# motoretc.net
KiCad netlist of a schematic drawn in EAGLE
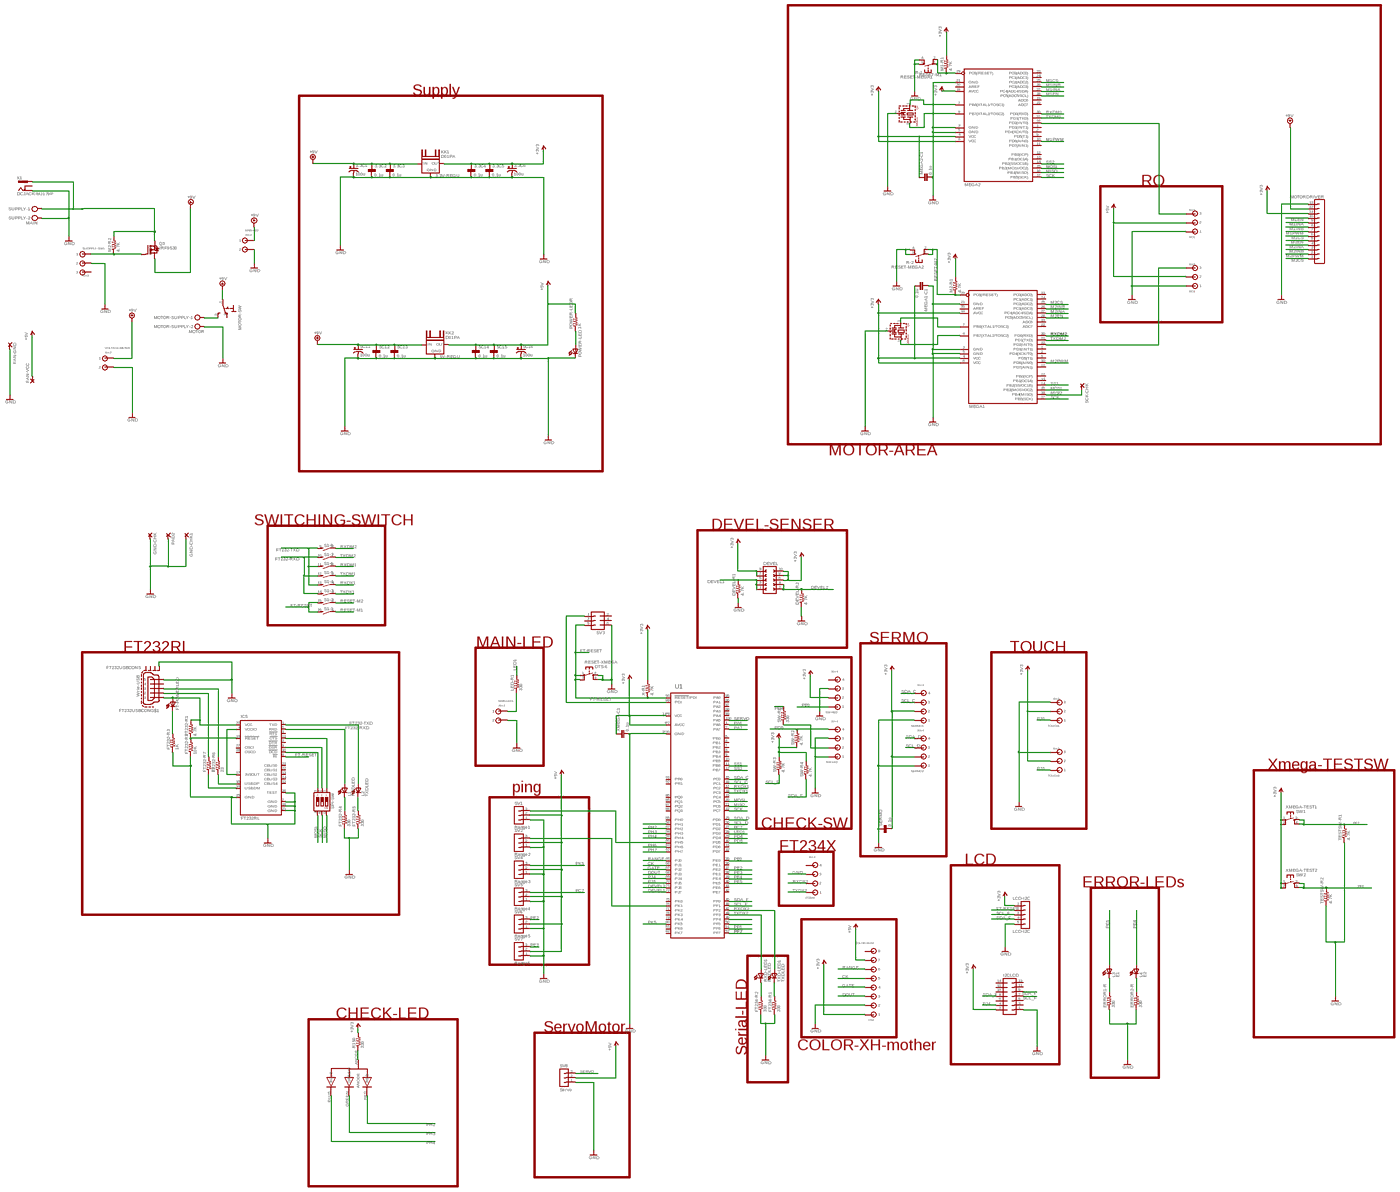
[diagram p0: schematic, sheet 1, overview]
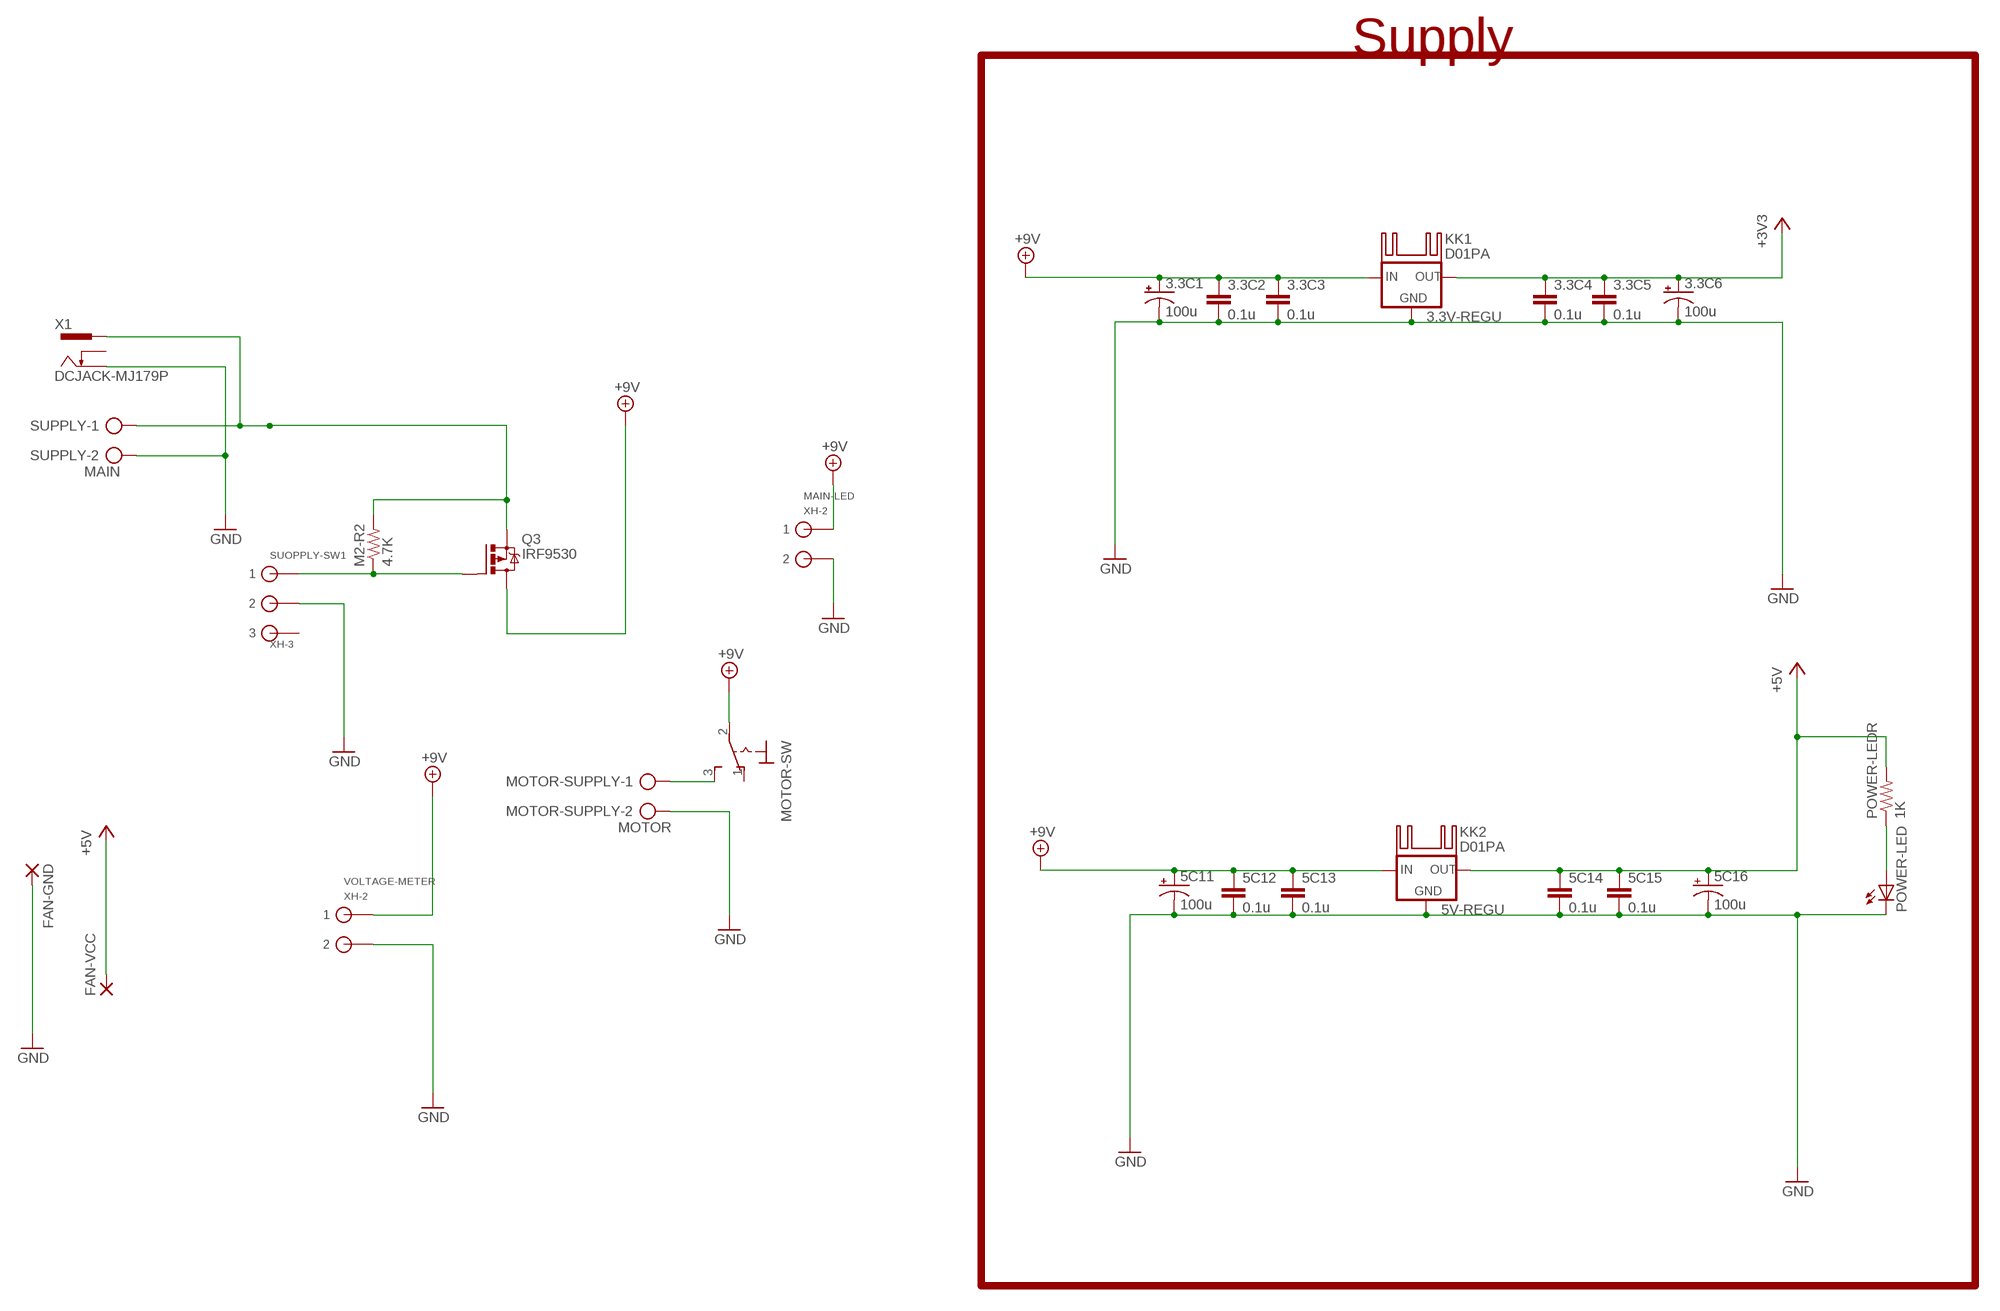
[diagram p1: schematic, sheet 1, part 1 of 4]
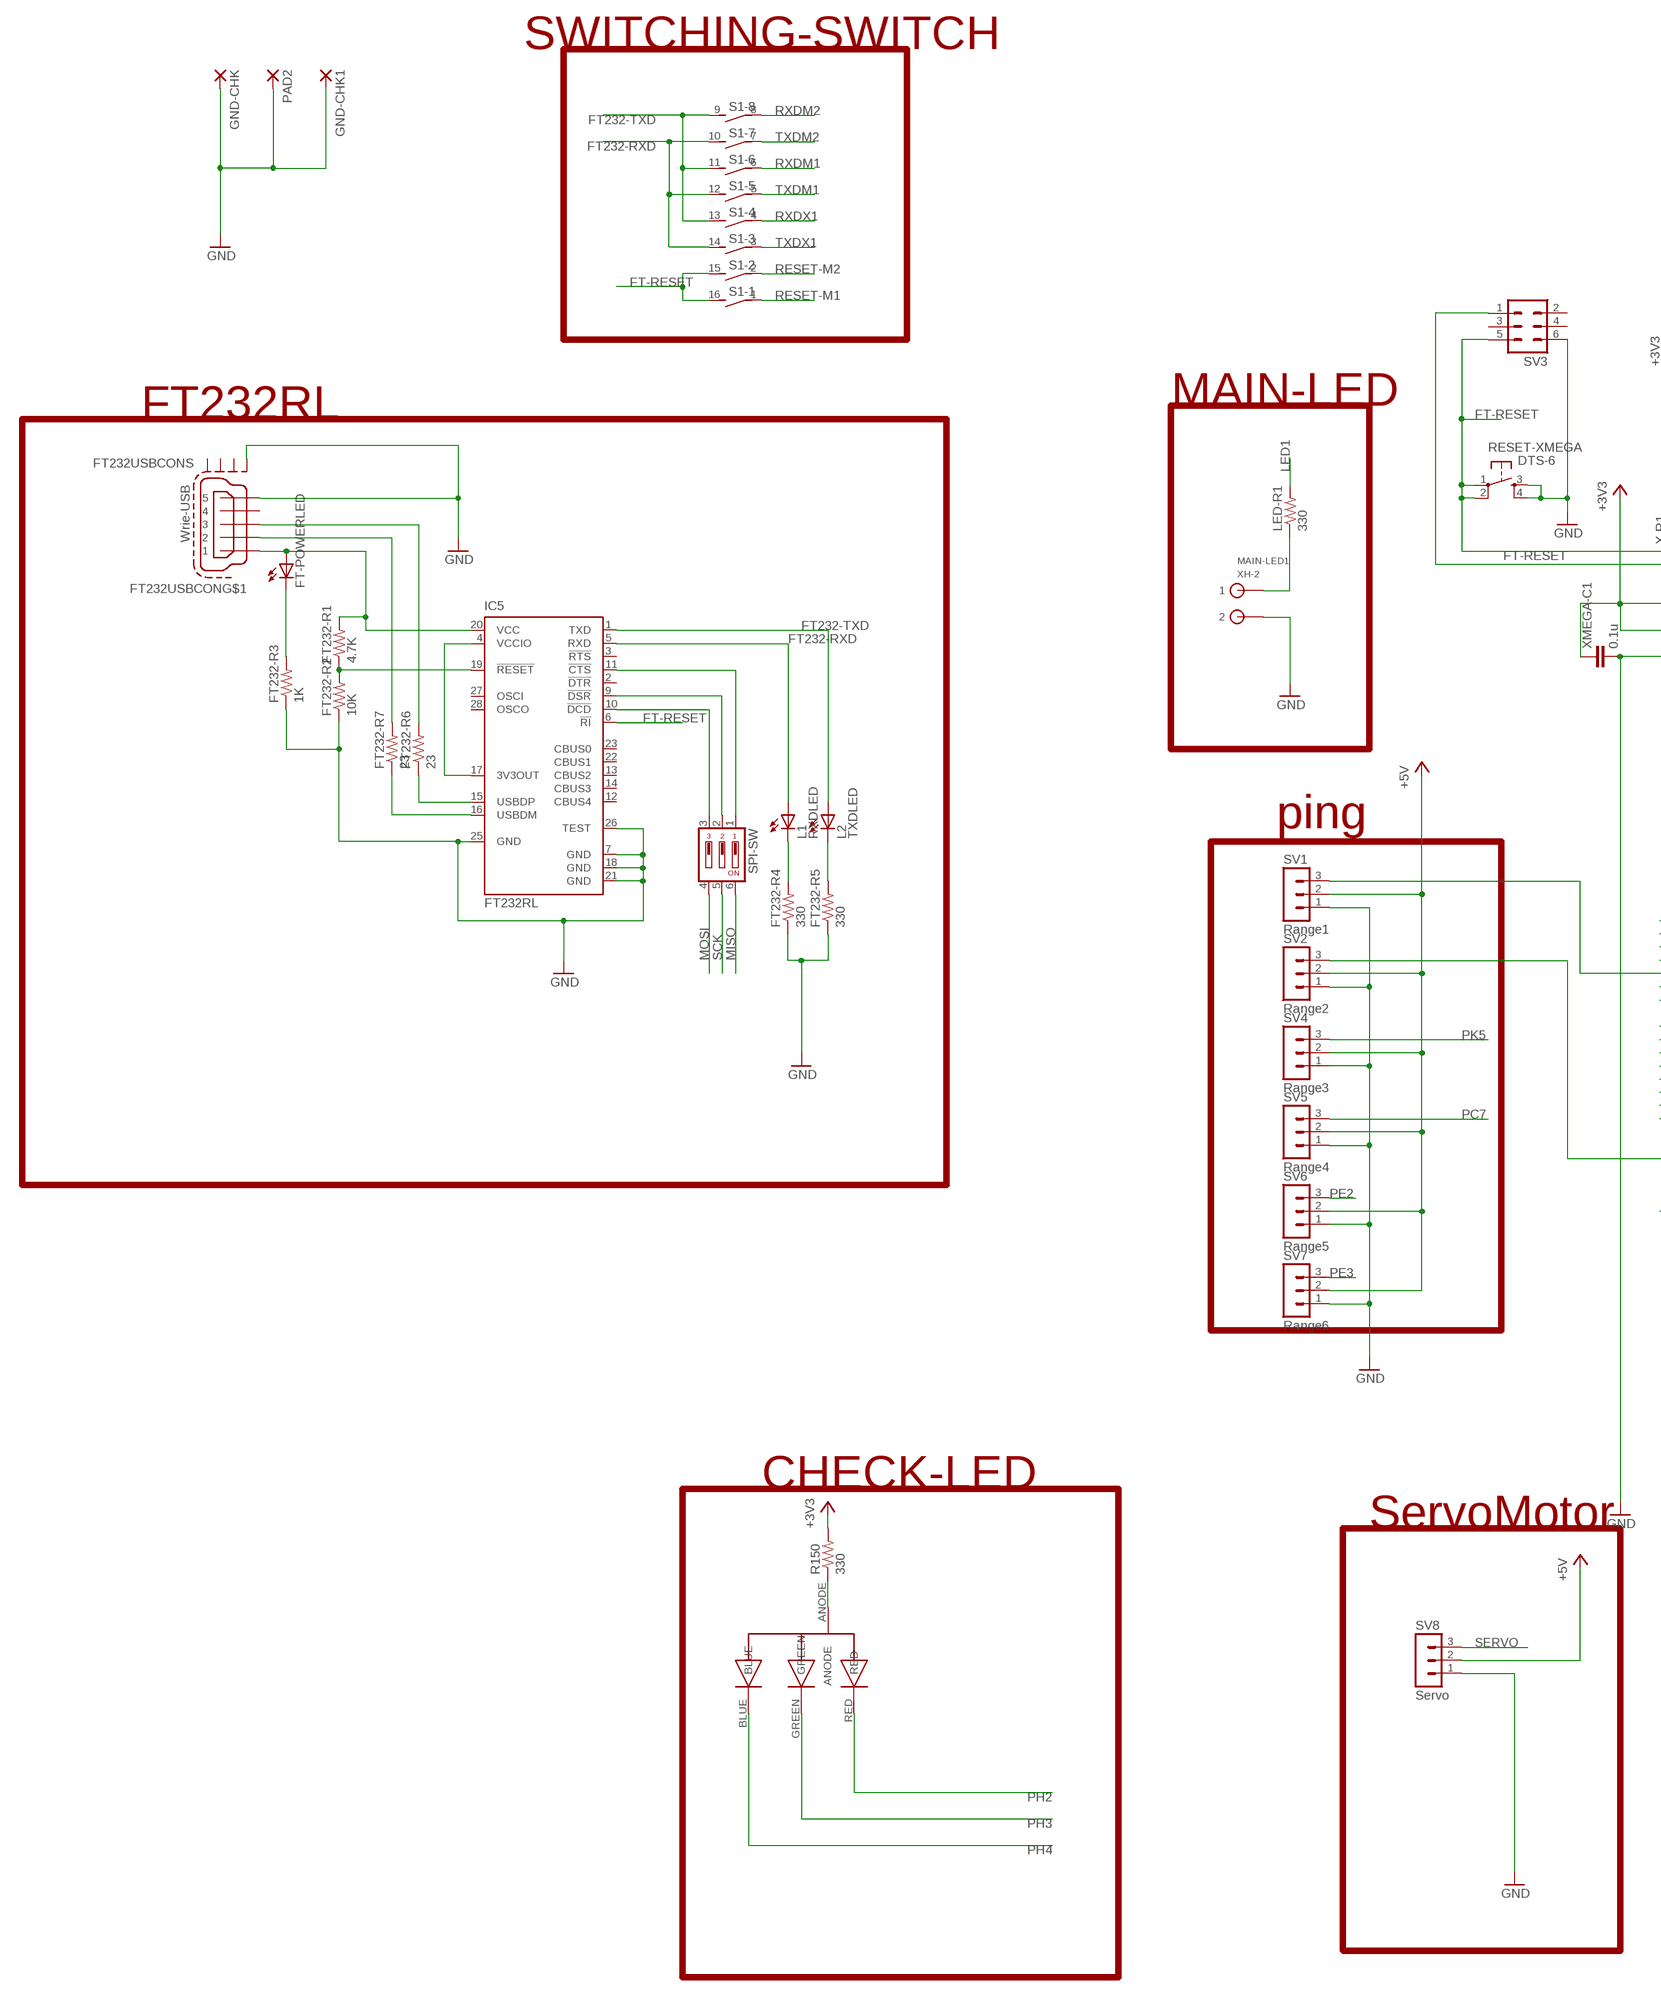
[diagram p2: schematic, sheet 1, part 2 of 4]
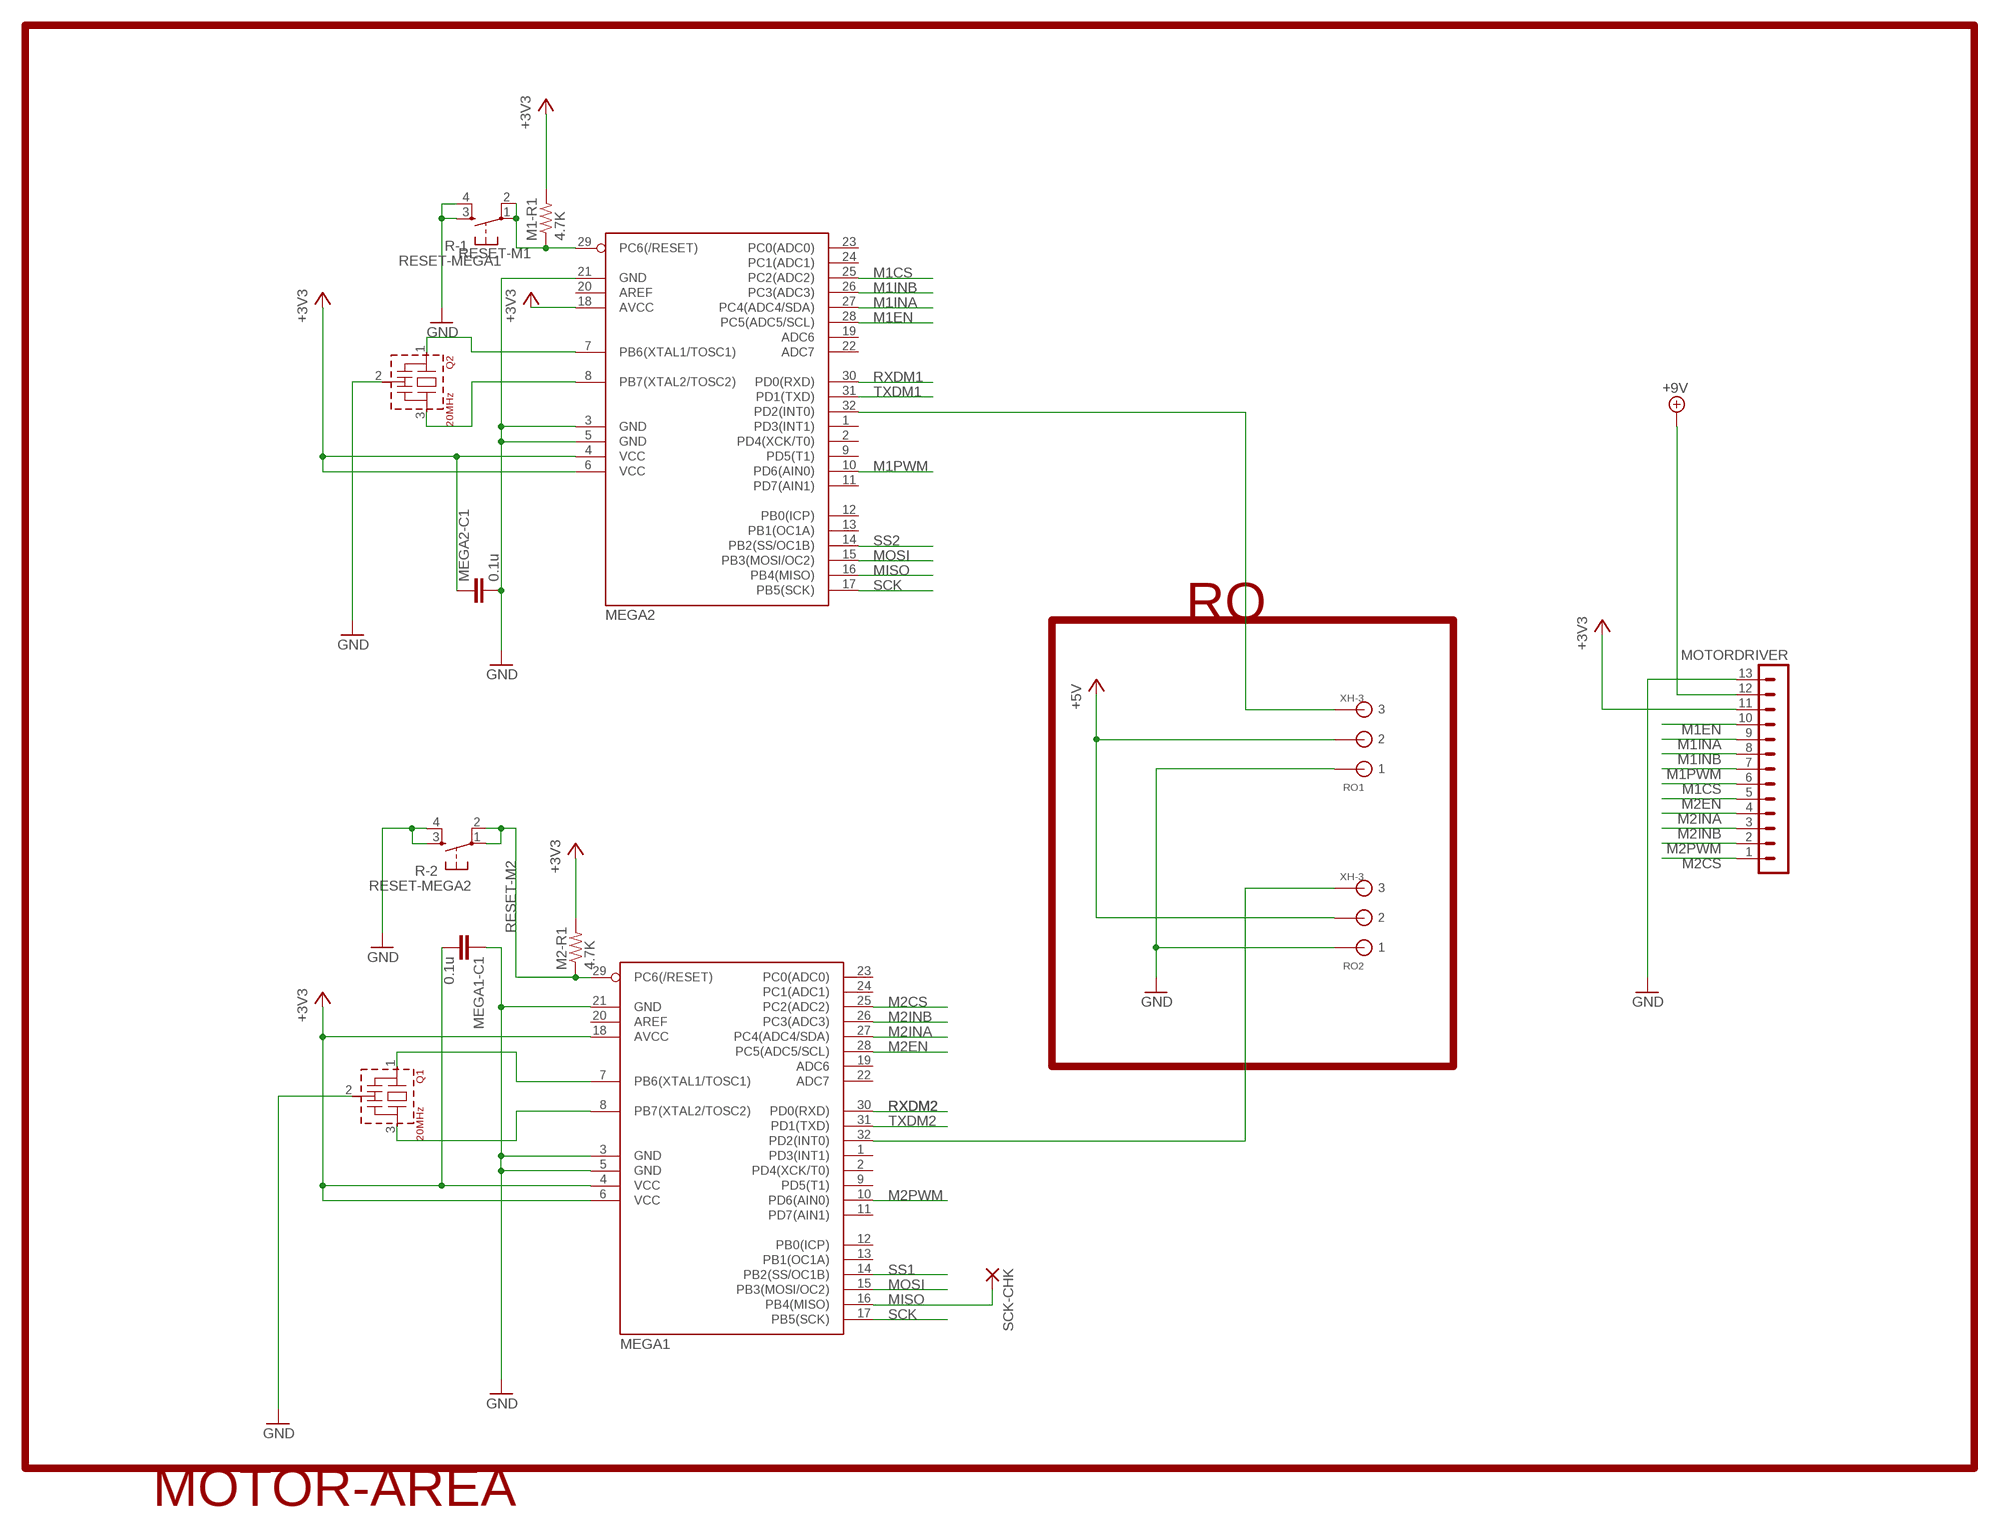
[diagram p3: schematic, sheet 1, part 3 of 4]
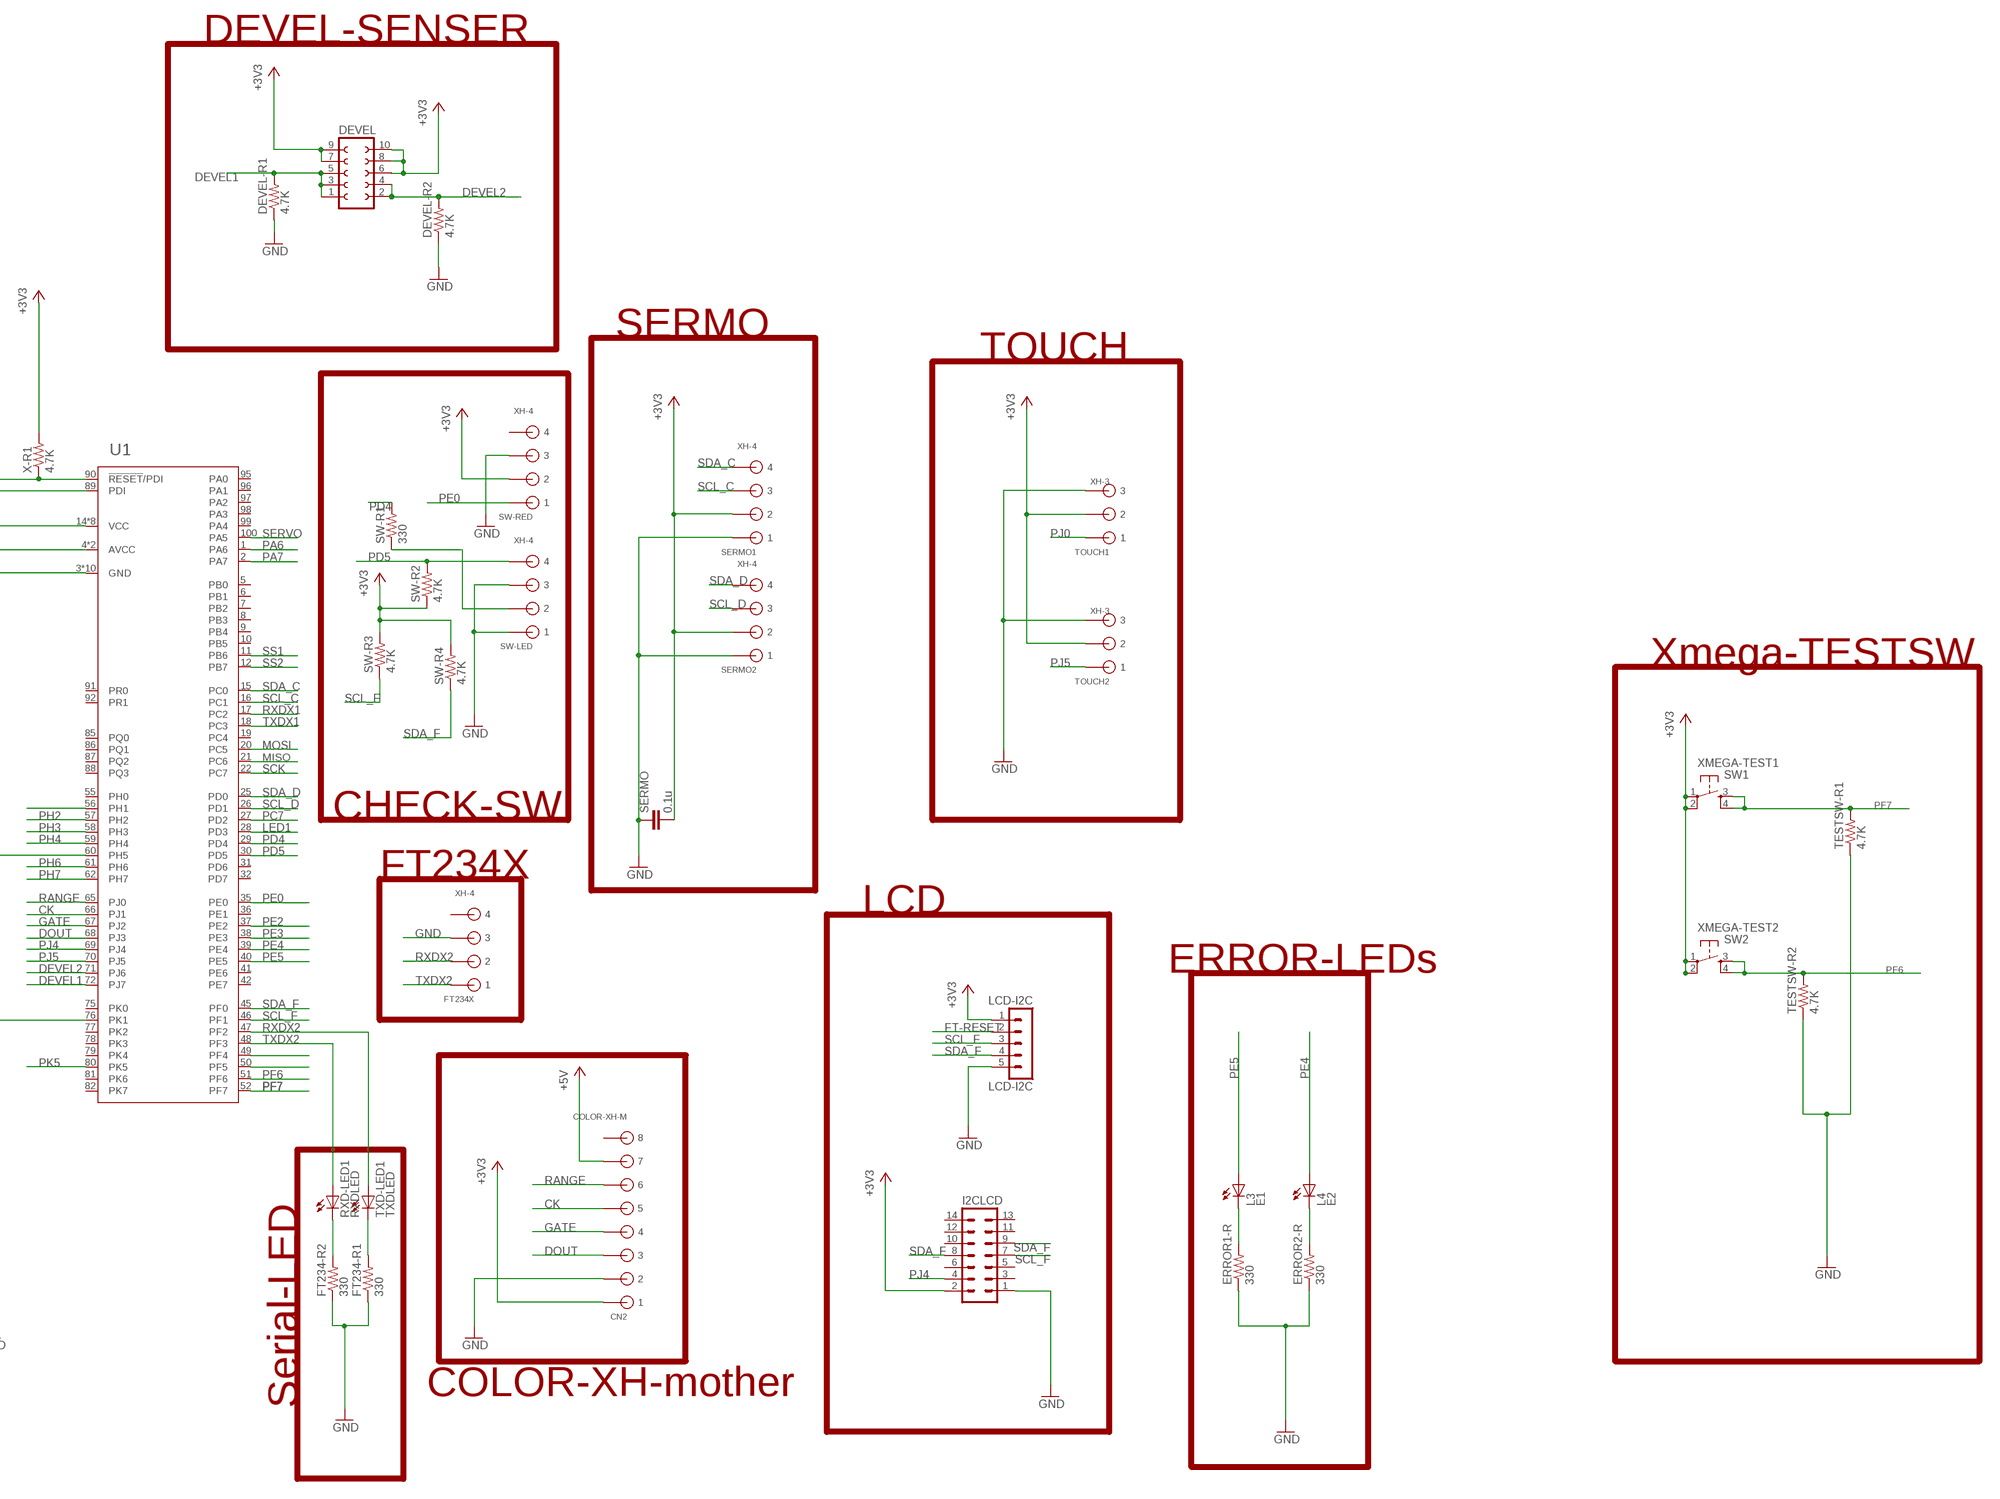
[diagram p4: schematic, sheet 1, part 4 of 4]

(export (version "E")
  (design (tool "Eeschema 10.0.6"))
  (components
    (comp (ref "3.3C1")
      (value "100u")
      (footprint "eagle-import:E2,5-6")
      (libsource (lib "eagle-import") (part "CPOL-USE2.5-6"))
    )
    (comp (ref "3.3C2")
      (value "0.1u")
      (footprint "eagle-import:C0805")
      (libsource (lib "eagle-import") (part "C-EUC0805"))
    )
    (comp (ref "3.3C3")
      (value "0.1u")
      (footprint "eagle-import:C0805")
      (libsource (lib "eagle-import") (part "C-EUC0805"))
    )
    (comp (ref "3.3C4")
      (value "0.1u")
      (footprint "eagle-import:C0805")
      (libsource (lib "eagle-import") (part "C-EUC0805"))
    )
    (comp (ref "3.3C5")
      (value "0.1u")
      (footprint "eagle-import:C0805")
      (libsource (lib "eagle-import") (part "C-EUC0805"))
    )
    (comp (ref "3.3C6")
      (value "100u")
      (footprint "eagle-import:E2,5-6")
      (libsource (lib "eagle-import") (part "CPOL-USE2.5-6"))
    )
    (comp (ref "3.3V-REGU")
      (value "78XXS")
      (footprint "eagle-import:78XXS")
      (libsource (lib "eagle-import") (part "78XXS"))
    )
    (comp (ref "5C11")
      (value "100u")
      (footprint "eagle-import:E2,5-6")
      (libsource (lib "eagle-import") (part "CPOL-USE2.5-6"))
    )
    (comp (ref "5C12")
      (value "0.1u")
      (footprint "eagle-import:C0805")
      (libsource (lib "eagle-import") (part "C-EUC0805"))
    )
    (comp (ref "5C13")
      (value "0.1u")
      (footprint "eagle-import:C0805")
      (libsource (lib "eagle-import") (part "C-EUC0805"))
    )
    (comp (ref "5C14")
      (value "0.1u")
      (footprint "eagle-import:C0805")
      (libsource (lib "eagle-import") (part "C-EUC0805"))
    )
    (comp (ref "5C15")
      (value "0.1u")
      (footprint "eagle-import:C0805")
      (libsource (lib "eagle-import") (part "C-EUC0805"))
    )
    (comp (ref "5C16")
      (value "100u")
      (footprint "eagle-import:E2,5-6")
      (libsource (lib "eagle-import") (part "CPOL-USE2.5-6"))
    )
    (comp (ref "5V-REGU")
      (value "78XXS")
      (footprint "eagle-import:78XXS")
      (libsource (lib "eagle-import") (part "78XXS"))
    )
    (comp (ref "CHECKLED")
      (value "OSTA71A1D-A")
      (footprint "eagle-import:OSTA71A1D-A")
      (libsource (lib "eagle-import") (part "OSTA71A1D-A"))
    )
    (comp (ref "CN2")
      (value "COLOR-XH-M")
      (footprint "eagle-import:CON8")
      (libsource (lib "eagle-import") (part "XH-8"))
    )
    (comp (ref "DEVEL")
      (value "FE05-2")
      (footprint "eagle-import:FE05-2")
      (libsource (lib "eagle-import") (part "FE05-2"))
    )
    (comp (ref "DEVEL-R1")
      (value "4.7K")
      (footprint "eagle-import:R0805")
      (libsource (lib "eagle-import") (part "R-US_R0805"))
    )
    (comp (ref "DEVEL-R2")
      (value "4.7K")
      (footprint "eagle-import:R0805")
      (libsource (lib "eagle-import") (part "R-US_R0805"))
    )
    (comp (ref "ERROR1-R")
      (value "330")
      (footprint "eagle-import:R0805")
      (libsource (lib "eagle-import") (part "R-US_R0805"))
    )
    (comp (ref "ERROR2-R")
      (value "330")
      (footprint "eagle-import:R0805")
      (libsource (lib "eagle-import") (part "R-US_R0805"))
    )
    (comp (ref "FAN-GND")
      (value "WIREPADSMD1,27-254")
      (footprint "eagle-import:SMD1,27-2,54")
      (libsource (lib "eagle-import") (part "WIREPADSMD1,27-254"))
    )
    (comp (ref "FAN-VCC")
      (value "WIREPADSMD1,27-254")
      (footprint "eagle-import:SMD1,27-2,54")
      (libsource (lib "eagle-import") (part "WIREPADSMD1,27-254"))
    )
    (comp (ref "FT-POWERLED")
      (value "LEDCHIPLED_0805")
      (footprint "eagle-import:CHIPLED_0805")
      (libsource (lib "eagle-import") (part "led_LEDCHIPLED_0805"))
    )
    (comp (ref "FT232-R1")
      (value "4.7K")
      (footprint "eagle-import:R0805")
      (libsource (lib "eagle-import") (part "R-US_R0805"))
    )
    (comp (ref "FT232-R2")
      (value "10K")
      (footprint "eagle-import:R0805")
      (libsource (lib "eagle-import") (part "R-US_R0805"))
    )
    (comp (ref "FT232-R3")
      (value "1K")
      (footprint "eagle-import:R0805")
      (libsource (lib "eagle-import") (part "R-US_R0805"))
    )
    (comp (ref "FT232-R4")
      (value "330")
      (footprint "eagle-import:R0805")
      (libsource (lib "eagle-import") (part "R-US_R0805"))
    )
    (comp (ref "FT232-R5")
      (value "330")
      (footprint "eagle-import:R0805")
      (libsource (lib "eagle-import") (part "R-US_R0805"))
    )
    (comp (ref "FT232-R6")
      (value "23")
      (footprint "eagle-import:R0805")
      (libsource (lib "eagle-import") (part "R-US_R0805"))
    )
    (comp (ref "FT232-R7")
      (value "23")
      (footprint "eagle-import:R0805")
      (libsource (lib "eagle-import") (part "R-US_R0805"))
    )
    (comp (ref "FT232USBCON")
      (value "Wrie-USB")
      (footprint "eagle-import:32005-201")
      (libsource (lib "eagle-import") (part "MINI-USB-SCHIELD-32005-201"))
    )
    (comp (ref "FT234-R1")
      (value "330")
      (footprint "eagle-import:R0805")
      (libsource (lib "eagle-import") (part "R-US_R0805"))
    )
    (comp (ref "FT234-R2")
      (value "330")
      (footprint "eagle-import:R0805")
      (libsource (lib "eagle-import") (part "R-US_R0805"))
    )
    (comp (ref "FT234X")
      (value "XH-4")
      (footprint "eagle-import:CON4")
      (libsource (lib "eagle-import") (part "XH-4"))
    )
    (comp (ref "GND-CHK")
      (value "2,15/1,0")
      (footprint "eagle-import:2,15_1,0")
      (libsource (lib "eagle-import") (part "2,15/1,0"))
    )
    (comp (ref "GND-CHK1")
      (value "2,15/1,0")
      (footprint "eagle-import:2,15_1,0")
      (libsource (lib "eagle-import") (part "2,15/1,0"))
    )
    (comp (ref "I2CLCD")
      (value "MA07-2")
      (footprint "eagle-import:MA07-2")
      (libsource (lib "eagle-import") (part "MA07-2"))
    )
    (comp (ref "IC5")
      (value "FT232RL")
      (footprint "eagle-import:SSOP28")
      (libsource (lib "eagle-import") (part "FT232RL"))
    )
    (comp (ref "KK1")
      (value "D01PA")
      (footprint "eagle-import:D01PA")
      (libsource (lib "eagle-import") (part "D01PA"))
    )
    (comp (ref "KK2")
      (value "D01PA")
      (footprint "eagle-import:D01PA")
      (libsource (lib "eagle-import") (part "D01PA"))
    )
    (comp (ref "L1")
      (value "RXDLED")
      (footprint "eagle-import:CHIPLED_0805")
      (libsource (lib "eagle-import") (part "led_LEDCHIPLED_0805"))
    )
    (comp (ref "L2")
      (value "TXDLED")
      (footprint "eagle-import:CHIPLED_0805")
      (libsource (lib "eagle-import") (part "led_LEDCHIPLED_0805"))
    )
    (comp (ref "L3")
      (value "E1")
      (footprint "eagle-import:LED5MM")
      (libsource (lib "eagle-import") (part "LED5MM"))
    )
    (comp (ref "L4")
      (value "E2")
      (footprint "eagle-import:LED5MM")
      (libsource (lib "eagle-import") (part "LED5MM"))
    )
    (comp (ref "LCD-I2C")
      (value "LCD-I2C")
      (footprint "eagle-import:MA05-1")
      (libsource (lib "eagle-import") (part "MA05-1"))
    )
    (comp (ref "LED-R1")
      (value "330")
      (footprint "eagle-import:R0805")
      (libsource (lib "eagle-import") (part "R-US_R0805"))
    )
    (comp (ref "M1-R1")
      (value "4.7K")
      (footprint "eagle-import:R0805")
      (libsource (lib "eagle-import") (part "R-US_R0805"))
    )
    (comp (ref "M2-R1")
      (value "4.7K")
      (footprint "eagle-import:R0805")
      (libsource (lib "eagle-import") (part "R-US_R0805"))
    )
    (comp (ref "M2-R2")
      (value "4.7K")
      (footprint "eagle-import:R0805")
      (libsource (lib "eagle-import") (part "R-US_R0805"))
    )
    (comp (ref "MAIN-LED")
      (value "XH-2")
      (footprint "eagle-import:CON2")
      (libsource (lib "eagle-import") (part "XH-2"))
    )
    (comp (ref "MAIN-LED1")
      (value "XH-2")
      (footprint "eagle-import:CON2")
      (libsource (lib "eagle-import") (part "XH-2"))
    )
    (comp (ref "MEGA1")
      (value "MEGA8-AI")
      (footprint "eagle-import:TQFP32-08")
      (fields (field (name "MPN") "ATMEGA8-16AU"))
      (libsource (lib "eagle-import") (part "MEGA8-AI"))
    )
    (comp (ref "MEGA1-C1")
      (value "0.1u")
      (footprint "eagle-import:C0805")
      (libsource (lib "eagle-import") (part "C-EUC0805"))
    )
    (comp (ref "MEGA2")
      (value "MEGA8-AI")
      (footprint "eagle-import:TQFP32-08")
      (fields (field (name "MPN") "ATMEGA8-16AU"))
      (libsource (lib "eagle-import") (part "MEGA8-AI"))
    )
    (comp (ref "MEGA2-C1")
      (value "0.1u")
      (footprint "eagle-import:C0805")
      (libsource (lib "eagle-import") (part "C-EUC0805"))
    )
    (comp (ref "MOTOR-SUPPLY")
      (value "MOTOR")
      (footprint "eagle-import:AK500_2")
      (libsource (lib "eagle-import") (part "AK500/2"))
    )
    (comp (ref "MOTOR-SW")
      (value "320-916")
      (footprint "eagle-import:320-916")
      (libsource (lib "eagle-import") (part "320-916"))
    )
    (comp (ref "MOTORDRIVER")
      (value "MA13-1")
      (footprint "eagle-import:MA13-1")
      (libsource (lib "eagle-import") (part "MA13-1"))
    )
    (comp (ref "PAD2")
      (value "SMD5")
      (footprint "eagle-import:SMD2,54-5,08")
      (libsource (lib "eagle-import") (part "SMD5"))
    )
    (comp (ref "POWER-LED")
      (value "LEDCHIPLED_0805")
      (footprint "eagle-import:CHIPLED_0805")
      (libsource (lib "eagle-import") (part "led_LEDCHIPLED_0805"))
    )
    (comp (ref "POWER-LEDR")
      (value "1K")
      (footprint "eagle-import:R0805")
      (libsource (lib "eagle-import") (part "R-US_R0805"))
    )
    (comp (ref "Q1")
      (value "20MHz")
      (footprint "eagle-import:CSTLS_X")
      (libsource (lib "eagle-import") (part "CSTLS_X"))
    )
    (comp (ref "Q2")
      (value "20MHz")
      (footprint "eagle-import:CSTLS_X")
      (libsource (lib "eagle-import") (part "CSTLS_X"))
    )
    (comp (ref "Q3")
      (value "IRF9530")
      (footprint "eagle-import:TO220BV")
      (libsource (lib "eagle-import") (part "IRF9530"))
    )
    (comp (ref "R150")
      (value "330")
      (footprint "eagle-import:R0805")
      (libsource (lib "eagle-import") (part "R-US_R0805"))
    )
    (comp (ref "RESET-MEGA1")
      (value "R-1")
      (footprint "eagle-import:DTS-6")
      (libsource (lib "eagle-import") (part "DTS-6"))
    )
    (comp (ref "RESET-MEGA2")
      (value "R-2")
      (footprint "eagle-import:DTS-6")
      (libsource (lib "eagle-import") (part "DTS-6"))
    )
    (comp (ref "RESET-XMEGA")
      (value "DTS-6")
      (footprint "eagle-import:DTS-6")
      (libsource (lib "eagle-import") (part "DTS-6"))
    )
    (comp (ref "RO1")
      (value "XH-3")
      (footprint "eagle-import:CON3")
      (libsource (lib "eagle-import") (part "XH-3"))
    )
    (comp (ref "RO2")
      (value "XH-3")
      (footprint "eagle-import:CON3")
      (libsource (lib "eagle-import") (part "XH-3"))
    )
    (comp (ref "RXD-LED1")
      (value "RXDLED")
      (footprint "eagle-import:CHIPLED_0805")
      (libsource (lib "eagle-import") (part "led_LEDCHIPLED_0805"))
    )
    (comp (ref "S1")
      (value "DIP08S")
      (footprint "eagle-import:DIP08S")
      (libsource (lib "eagle-import") (part "DIP08S"))
    )
    (comp (ref "SCK-CHK")
      (value "2,15/1,0")
      (footprint "eagle-import:2,15_1,0")
      (libsource (lib "eagle-import") (part "2,15/1,0"))
    )
    (comp (ref "SERMO")
      (value "0.1u")
      (footprint "eagle-import:C0805")
      (libsource (lib "eagle-import") (part "C-EUC0805"))
    )
    (comp (ref "SERMO1")
      (value "XH-4")
      (footprint "eagle-import:CON4")
      (libsource (lib "eagle-import") (part "XH-4"))
    )
    (comp (ref "SERMO2")
      (value "XH-4")
      (footprint "eagle-import:CON4")
      (libsource (lib "eagle-import") (part "XH-4"))
    )
    (comp (ref "SPI-SW")
      (value "DIP03YL")
      (footprint "eagle-import:DIP03YL")
      (libsource (lib "eagle-import") (part "DIP03YL"))
    )
    (comp (ref "SUOPPLY-SW1")
      (value "XH-3")
      (footprint "eagle-import:CON3")
      (libsource (lib "eagle-import") (part "XH-3"))
    )
    (comp (ref "SUPPLY")
      (value "MAIN")
      (footprint "eagle-import:AK500_2")
      (libsource (lib "eagle-import") (part "AK500/2"))
    )
    (comp (ref "SV1")
      (value "Range1")
      (footprint "eagle-import:MA03-1")
      (libsource (lib "eagle-import") (part "MA03-1"))
    )
    (comp (ref "SV2")
      (value "Range2")
      (footprint "eagle-import:MA03-1")
      (libsource (lib "eagle-import") (part "MA03-1"))
    )
    (comp (ref "SV3")
      (value "ML6")
      (footprint "eagle-import:ML6")
      (libsource (lib "eagle-import") (part "ML6"))
    )
    (comp (ref "SV4")
      (value "Range3")
      (footprint "eagle-import:MA03-1")
      (libsource (lib "eagle-import") (part "MA03-1"))
    )
    (comp (ref "SV5")
      (value "Range4")
      (footprint "eagle-import:MA03-1")
      (libsource (lib "eagle-import") (part "MA03-1"))
    )
    (comp (ref "SV6")
      (value "Range5")
      (footprint "eagle-import:MA03-1")
      (libsource (lib "eagle-import") (part "MA03-1"))
    )
    (comp (ref "SV7")
      (value "Range6")
      (footprint "eagle-import:MA03-1")
      (libsource (lib "eagle-import") (part "MA03-1"))
    )
    (comp (ref "SV8")
      (value "Servo")
      (footprint "eagle-import:MA03-1")
      (libsource (lib "eagle-import") (part "MA03-1"))
    )
    (comp (ref "SW-LED")
      (value "XH-4")
      (footprint "eagle-import:CON4")
      (libsource (lib "eagle-import") (part "XH-4"))
    )
    (comp (ref "SW-R1")
      (value "330")
      (footprint "eagle-import:R0805")
      (libsource (lib "eagle-import") (part "R-US_R0805"))
    )
    (comp (ref "SW-R2")
      (value "4.7K")
      (footprint "eagle-import:R0805")
      (libsource (lib "eagle-import") (part "R-US_R0805"))
    )
    (comp (ref "SW-R3")
      (value "4.7K")
      (footprint "eagle-import:R0805")
      (libsource (lib "eagle-import") (part "R-US_R0805"))
    )
    (comp (ref "SW-R4")
      (value "4.7K")
      (footprint "eagle-import:R0805")
      (libsource (lib "eagle-import") (part "R-US_R0805"))
    )
    (comp (ref "SW-RED")
      (value "XH-4")
      (footprint "eagle-import:CON4")
      (libsource (lib "eagle-import") (part "XH-4"))
    )
    (comp (ref "TESTSW-R1")
      (value "4.7K")
      (footprint "eagle-import:R0805")
      (libsource (lib "eagle-import") (part "R-US_R0805"))
    )
    (comp (ref "TESTSW-R2")
      (value "4.7K")
      (footprint "eagle-import:R0805")
      (libsource (lib "eagle-import") (part "R-US_R0805"))
    )
    (comp (ref "TOUCH1")
      (value "XH-3")
      (footprint "eagle-import:CON3")
      (libsource (lib "eagle-import") (part "XH-3"))
    )
    (comp (ref "TOUCH2")
      (value "XH-3")
      (footprint "eagle-import:CON3")
      (libsource (lib "eagle-import") (part "XH-3"))
    )
    (comp (ref "TXD-LED1")
      (value "TXDLED")
      (footprint "eagle-import:CHIPLED_0805")
      (libsource (lib "eagle-import") (part "led_LEDCHIPLED_0805"))
    )
    (comp (ref "U1")
      (value "ATXMEGA128A1U-AU")
      (footprint "eagle-import:TQFP-100A-100")
      (libsource (lib "eagle-import") (part "ATXMEGA128A1U-AU"))
    )
    (comp (ref "VOLTAGE-METER")
      (value "XH-2")
      (footprint "eagle-import:CON2")
      (libsource (lib "eagle-import") (part "XH-2"))
    )
    (comp (ref "X-R1")
      (value "4.7K")
      (footprint "eagle-import:R0805")
      (libsource (lib "eagle-import") (part "R-US_R0805"))
    )
    (comp (ref "X1")
      (value "DCJACK-MJ179P")
      (footprint "eagle-import:MJ-179P")
      (libsource (lib "eagle-import") (part "DCJACK-MJ179P"))
    )
    (comp (ref "XMEGA-C1")
      (value "0.1u")
      (footprint "eagle-import:C0805")
      (libsource (lib "eagle-import") (part "C-EUC0805"))
    )
    (comp (ref "XMEGA-TEST1")
      (value "SW1")
      (footprint "eagle-import:DTS-6")
      (libsource (lib "eagle-import") (part "DTS-6"))
    )
    (comp (ref "XMEGA-TEST2")
      (value "SW2")
      (footprint "eagle-import:DTS-6")
      (libsource (lib "eagle-import") (part "DTS-6"))
    )
  )
  (nets
    (net (code "1") (name "+3V3") (class "Default")
      (node (ref "3.3C4") (pin "1") (pinfunction "1_1") (pintype "passive"))
      (node (ref "3.3C5") (pin "1") (pinfunction "1_1") (pintype "passive"))
      (node (ref "3.3C6") (pin "+") (pinfunction "+_+") (pintype "passive"))
      (node (ref "3.3V-REGU") (pin "OUT") (pinfunction "OUT_OUT") (pintype "passive"))
      (node (ref "CN2") (pin "P$1") (pinfunction "1_P$1") (pintype "bidirectional"))
      (node (ref "DEVEL") (pin "10") (pinfunction "10_10") (pintype "passive"))
      (node (ref "DEVEL") (pin "6") (pinfunction "6_6") (pintype "passive"))
      (node (ref "DEVEL") (pin "7") (pinfunction "7_7") (pintype "passive"))
      (node (ref "DEVEL") (pin "8") (pinfunction "8_8") (pintype "passive"))
      (node (ref "DEVEL") (pin "9") (pinfunction "9_9") (pintype "passive"))
      (node (ref "I2CLCD") (pin "2") (pinfunction "2_2") (pintype "passive"))
      (node (ref "LCD-I2C") (pin "1") (pinfunction "1_1") (pintype "passive"))
      (node (ref "M1-R1") (pin "2") (pinfunction "2_2") (pintype "passive"))
      (node (ref "M2-R1") (pin "2") (pinfunction "2_2") (pintype "passive"))
      (node (ref "MEGA1") (pin "18") (pinfunction "AVCC_18") (pintype "power_in"))
      (node (ref "MEGA1") (pin "4") (pinfunction "VCC_4") (pintype "power_in"))
      (node (ref "MEGA1") (pin "6") (pinfunction "VCC_6") (pintype "power_in"))
      (node (ref "MEGA1-C1") (pin "2") (pinfunction "2_2") (pintype "passive"))
      (node (ref "MEGA2") (pin "18") (pinfunction "AVCC_18") (pintype "power_in"))
      (node (ref "MEGA2") (pin "4") (pinfunction "VCC_4") (pintype "power_in"))
      (node (ref "MEGA2") (pin "6") (pinfunction "VCC_6") (pintype "power_in"))
      (node (ref "MEGA2-C1") (pin "1") (pinfunction "1_1") (pintype "passive"))
      (node (ref "MOTORDRIVER") (pin "11") (pinfunction "11_11") (pintype "passive"))
      (node (ref "R150") (pin "2") (pinfunction "2_2") (pintype "passive"))
      (node (ref "SERMO") (pin "2") (pinfunction "2_2") (pintype "passive"))
      (node (ref "SERMO1") (pin "P$2") (pinfunction "2_P$2") (pintype "bidirectional"))
      (node (ref "SERMO2") (pin "P$2") (pinfunction "2_P$2") (pintype "bidirectional"))
      (node (ref "SW-R2") (pin "1") (pinfunction "1_1") (pintype "passive"))
      (node (ref "SW-R3") (pin "2") (pinfunction "2_2") (pintype "passive"))
      (node (ref "SW-R4") (pin "2") (pinfunction "2_2") (pintype "passive"))
      (node (ref "SW-RED") (pin "P$2") (pinfunction "2_P$2") (pintype "bidirectional"))
      (node (ref "TOUCH1") (pin "P$2") (pinfunction "2_P$2") (pintype "bidirectional"))
      (node (ref "TOUCH2") (pin "P$2") (pinfunction "2_P$2") (pintype "bidirectional"))
      (node (ref "U1") (pin "14") (pinfunction "VCC_14") (pintype "power_in"))
      (node (ref "U1") (pin "24") (pinfunction "VCC_24") (pintype "power_in"))
      (node (ref "U1") (pin "34") (pinfunction "VCC_34") (pintype "power_in"))
      (node (ref "U1") (pin "4") (pinfunction "AVCC_4") (pintype "power_in"))
      (node (ref "U1") (pin "44") (pinfunction "VCC_44") (pintype "power_in"))
      (node (ref "U1") (pin "54") (pinfunction "VCC_54") (pintype "power_in"))
      (node (ref "U1") (pin "64") (pinfunction "VCC_64") (pintype "power_in"))
      (node (ref "U1") (pin "74") (pinfunction "VCC_74") (pintype "power_in"))
      (node (ref "U1") (pin "83") (pinfunction "VCC_83") (pintype "power_in"))
      (node (ref "U1") (pin "94") (pinfunction "AVCC_94") (pintype "power_in"))
      (node (ref "X-R1") (pin "2") (pinfunction "2_2") (pintype "passive"))
      (node (ref "XMEGA-C1") (pin "1") (pinfunction "1_1") (pintype "passive"))
      (node (ref "XMEGA-TEST1") (pin "1") (pinfunction "1_1") (pintype "passive"))
      (node (ref "XMEGA-TEST1") (pin "2") (pinfunction "2_2") (pintype "passive"))
      (node (ref "XMEGA-TEST2") (pin "1") (pinfunction "1_1") (pintype "passive"))
      (node (ref "XMEGA-TEST2") (pin "2") (pinfunction "2_2") (pintype "passive"))
    )
    (net (code "2") (name "+5V") (class "Default")
      (node (ref "5C14") (pin "1") (pinfunction "1_1") (pintype "passive"))
      (node (ref "5C15") (pin "1") (pinfunction "1_1") (pintype "passive"))
      (node (ref "5C16") (pin "+") (pinfunction "+_+") (pintype "passive"))
      (node (ref "5V-REGU") (pin "OUT") (pinfunction "OUT_OUT") (pintype "passive"))
      (node (ref "CN2") (pin "P$7") (pinfunction "7_P$7") (pintype "bidirectional"))
      (node (ref "FAN-VCC") (pin "1") (pinfunction "P_1") (pintype "passive"))
      (node (ref "POWER-LEDR") (pin "2") (pinfunction "2_2") (pintype "passive"))
      (node (ref "RO1") (pin "P$2") (pinfunction "2_P$2") (pintype "bidirectional"))
      (node (ref "RO2") (pin "P$2") (pinfunction "2_P$2") (pintype "bidirectional"))
      (node (ref "SV1") (pin "2") (pinfunction "2_2") (pintype "passive"))
      (node (ref "SV2") (pin "2") (pinfunction "2_2") (pintype "passive"))
      (node (ref "SV4") (pin "2") (pinfunction "2_2") (pintype "passive"))
      (node (ref "SV5") (pin "2") (pinfunction "2_2") (pintype "passive"))
      (node (ref "SV6") (pin "2") (pinfunction "2_2") (pintype "passive"))
      (node (ref "SV7") (pin "2") (pinfunction "2_2") (pintype "passive"))
      (node (ref "SV8") (pin "2") (pinfunction "2_2") (pintype "passive"))
    )
    (net (code "3") (name "+9V") (class "Default")
      (node (ref "3.3C1") (pin "+") (pinfunction "+_+") (pintype "passive"))
      (node (ref "3.3C2") (pin "1") (pinfunction "1_1") (pintype "passive"))
      (node (ref "3.3C3") (pin "1") (pinfunction "1_1") (pintype "passive"))
      (node (ref "3.3V-REGU") (pin "IN") (pinfunction "IN_IN") (pintype "input"))
      (node (ref "5C11") (pin "+") (pinfunction "+_+") (pintype "passive"))
      (node (ref "5C12") (pin "1") (pinfunction "1_1") (pintype "passive"))
      (node (ref "5C13") (pin "1") (pinfunction "1_1") (pintype "passive"))
      (node (ref "5V-REGU") (pin "IN") (pinfunction "IN_IN") (pintype "input"))
      (node (ref "MAIN-LED") (pin "P$1") (pinfunction "1_P$1") (pintype "bidirectional"))
      (node (ref "MOTOR-SW") (pin "2") (pinfunction "P_2") (pintype "passive"))
      (node (ref "MOTORDRIVER") (pin "12") (pinfunction "12_12") (pintype "passive"))
      (node (ref "Q3") (pin "D") (pinfunction "D_D") (pintype "passive"))
      (node (ref "VOLTAGE-METER") (pin "P$1") (pinfunction "1_P$1") (pintype "bidirectional"))
    )
    (net (code "4") (name "/CK") (class "Default")
      (node (ref "CN2") (pin "P$5") (pinfunction "5_P$5") (pintype "bidirectional"))
      (node (ref "U1") (pin "66") (pinfunction "PJ1_66") (pintype "bidirectional"))
    )
    (net (code "5") (name "/DEVEL1") (class "Default")
      (node (ref "DEVEL") (pin "1") (pinfunction "1_1") (pintype "passive"))
      (node (ref "DEVEL") (pin "3") (pinfunction "3_3") (pintype "passive"))
      (node (ref "DEVEL") (pin "5") (pinfunction "5_5") (pintype "passive"))
      (node (ref "DEVEL-R1") (pin "2") (pinfunction "2_2") (pintype "passive"))
      (node (ref "U1") (pin "72") (pinfunction "PJ7_72") (pintype "bidirectional"))
    )
    (net (code "6") (name "/DEVEL2") (class "Default")
      (node (ref "DEVEL") (pin "2") (pinfunction "2_2") (pintype "passive"))
      (node (ref "DEVEL") (pin "4") (pinfunction "4_4") (pintype "passive"))
      (node (ref "DEVEL-R2") (pin "2") (pinfunction "2_2") (pintype "passive"))
      (node (ref "U1") (pin "71") (pinfunction "PJ6_71") (pintype "bidirectional"))
    )
    (net (code "7") (name "/DOUT") (class "Default")
      (node (ref "CN2") (pin "P$3") (pinfunction "3_P$3") (pintype "bidirectional"))
      (node (ref "U1") (pin "68") (pinfunction "PJ3_68") (pintype "bidirectional"))
    )
    (net (code "8") (name "/FT-RESET") (class "Default")
      (node (ref "IC5") (pin "6") (pinfunction "~{RI}_6") (pintype "input"))
      (node (ref "LCD-I2C") (pin "2") (pinfunction "2_2") (pintype "passive"))
      (node (ref "RESET-XMEGA") (pin "1") (pinfunction "1_1") (pintype "passive"))
      (node (ref "RESET-XMEGA") (pin "2") (pinfunction "2_2") (pintype "passive"))
      (node (ref "S1") (pin "15") (pinfunction "2_15") (pintype "passive"))
      (node (ref "S1") (pin "16") (pinfunction "2_16") (pintype "passive"))
      (node (ref "SV3") (pin "5") (pinfunction "5_5") (pintype "passive"))
      (node (ref "U1") (pin "90") (pinfunction "~{RESET}/PDI_90") (pintype "bidirectional"))
      (node (ref "X-R1") (pin "1") (pinfunction "1_1") (pintype "passive"))
    )
    (net (code "9") (name "/FT232-RXD") (class "Default")
      (node (ref "IC5") (pin "5") (pinfunction "RXD_5") (pintype "input"))
      (node (ref "L1") (pin "A") (pinfunction "A_A") (pintype "passive"))
      (node (ref "S1") (pin "10") (pinfunction "2_10") (pintype "passive"))
      (node (ref "S1") (pin "12") (pinfunction "2_12") (pintype "passive"))
      (node (ref "S1") (pin "14") (pinfunction "2_14") (pintype "passive"))
    )
    (net (code "10") (name "/FT232-TXD") (class "Default")
      (node (ref "IC5") (pin "1") (pinfunction "TXD_1") (pintype "output"))
      (node (ref "L2") (pin "A") (pinfunction "A_A") (pintype "passive"))
      (node (ref "S1") (pin "11") (pinfunction "2_11") (pintype "passive"))
      (node (ref "S1") (pin "13") (pinfunction "2_13") (pintype "passive"))
      (node (ref "S1") (pin "9") (pinfunction "2_9") (pintype "passive"))
    )
    (net (code "11") (name "/GATE") (class "Default")
      (node (ref "CN2") (pin "P$4") (pinfunction "4_P$4") (pintype "bidirectional"))
      (node (ref "U1") (pin "67") (pinfunction "PJ2_67") (pintype "bidirectional"))
    )
    (net (code "12") (name "/LED1") (class "Default")
      (node (ref "LED-R1") (pin "2") (pinfunction "2_2") (pintype "passive"))
      (node (ref "U1") (pin "28") (pinfunction "PD3_28") (pintype "bidirectional"))
    )
    (net (code "13") (name "/M1CS") (class "Default")
      (node (ref "MEGA2") (pin "25") (pinfunction "PC2(ADC2)_25") (pintype "bidirectional"))
      (node (ref "MOTORDRIVER") (pin "6") (pinfunction "6_6") (pintype "passive"))
    )
    (net (code "14") (name "/M1EN") (class "Default")
      (node (ref "MEGA2") (pin "28") (pinfunction "PC5(ADC5/SCL)_28") (pintype "bidirectional"))
      (node (ref "MOTORDRIVER") (pin "10") (pinfunction "10_10") (pintype "passive"))
    )
    (net (code "15") (name "/M1INA") (class "Default")
      (node (ref "MEGA2") (pin "27") (pinfunction "PC4(ADC4/SDA)_27") (pintype "bidirectional"))
      (node (ref "MOTORDRIVER") (pin "9") (pinfunction "9_9") (pintype "passive"))
    )
    (net (code "16") (name "/M1INB") (class "Default")
      (node (ref "MEGA2") (pin "26") (pinfunction "PC3(ADC3)_26") (pintype "bidirectional"))
      (node (ref "MOTORDRIVER") (pin "8") (pinfunction "8_8") (pintype "passive"))
    )
    (net (code "17") (name "/M1PWM") (class "Default")
      (node (ref "MEGA2") (pin "10") (pinfunction "PD6(AIN0)_10") (pintype "bidirectional"))
      (node (ref "MOTORDRIVER") (pin "7") (pinfunction "7_7") (pintype "passive"))
    )
    (net (code "18") (name "/M2CS") (class "Default")
      (node (ref "MEGA1") (pin "25") (pinfunction "PC2(ADC2)_25") (pintype "bidirectional"))
      (node (ref "MOTORDRIVER") (pin "1") (pinfunction "1_1") (pintype "passive"))
    )
    (net (code "19") (name "/M2EN") (class "Default")
      (node (ref "MEGA1") (pin "28") (pinfunction "PC5(ADC5/SCL)_28") (pintype "bidirectional"))
      (node (ref "MOTORDRIVER") (pin "5") (pinfunction "5_5") (pintype "passive"))
    )
    (net (code "20") (name "/M2INA") (class "Default")
      (node (ref "MEGA1") (pin "27") (pinfunction "PC4(ADC4/SDA)_27") (pintype "bidirectional"))
      (node (ref "MOTORDRIVER") (pin "4") (pinfunction "4_4") (pintype "passive"))
    )
    (net (code "21") (name "/M2INB") (class "Default")
      (node (ref "MEGA1") (pin "26") (pinfunction "PC3(ADC3)_26") (pintype "bidirectional"))
      (node (ref "MOTORDRIVER") (pin "3") (pinfunction "3_3") (pintype "passive"))
    )
    (net (code "22") (name "/M2PWM") (class "Default")
      (node (ref "MEGA1") (pin "10") (pinfunction "PD6(AIN0)_10") (pintype "bidirectional"))
      (node (ref "MOTORDRIVER") (pin "2") (pinfunction "2_2") (pintype "passive"))
    )
    (net (code "23") (name "/MISO") (class "Default")
      (node (ref "MEGA1") (pin "16") (pinfunction "PB4(MISO)_16") (pintype "bidirectional"))
      (node (ref "MEGA2") (pin "16") (pinfunction "PB4(MISO)_16") (pintype "bidirectional"))
      (node (ref "SCK-CHK") (pin "1") (pinfunction "P_1") (pintype "passive"))
      (node (ref "SPI-SW") (pin "6") (pinfunction "6_6") (pintype "passive"))
      (node (ref "U1") (pin "21") (pinfunction "PC6_21") (pintype "bidirectional"))
    )
    (net (code "24") (name "/MOSI") (class "Default")
      (node (ref "MEGA1") (pin "15") (pinfunction "PB3(MOSI/OC2)_15") (pintype "bidirectional"))
      (node (ref "MEGA2") (pin "15") (pinfunction "PB3(MOSI/OC2)_15") (pintype "bidirectional"))
      (node (ref "SPI-SW") (pin "4") (pinfunction "4_4") (pintype "passive"))
      (node (ref "U1") (pin "20") (pinfunction "PC5_20") (pintype "bidirectional"))
    )
    (net (code "25") (name "/PA6") (class "Default")
      (node (ref "U1") (pin "1") (pinfunction "PA6_1") (pintype "bidirectional"))
    )
    (net (code "26") (name "/PA7") (class "Default")
      (node (ref "U1") (pin "2") (pinfunction "PA7_2") (pintype "bidirectional"))
    )
    (net (code "27") (name "/PC7") (class "Default")
      (node (ref "SV5") (pin "3") (pinfunction "3_3") (pintype "passive"))
      (node (ref "U1") (pin "27") (pinfunction "PD2_27") (pintype "bidirectional"))
    )
    (net (code "28") (name "/PD4") (class "Default")
      (node (ref "SW-R1") (pin "2") (pinfunction "2_2") (pintype "passive"))
      (node (ref "U1") (pin "29") (pinfunction "PD4_29") (pintype "bidirectional"))
    )
    (net (code "29") (name "/PD5") (class "Default")
      (node (ref "SW-LED") (pin "P$4") (pinfunction "4_P$4") (pintype "bidirectional"))
      (node (ref "SW-R2") (pin "2") (pinfunction "2_2") (pintype "passive"))
      (node (ref "U1") (pin "30") (pinfunction "PD5_30") (pintype "bidirectional"))
    )
    (net (code "30") (name "/PE0") (class "Default")
      (node (ref "SW-RED") (pin "P$1") (pinfunction "1_P$1") (pintype "bidirectional"))
      (node (ref "U1") (pin "35") (pinfunction "PE0_35") (pintype "bidirectional"))
    )
    (net (code "31") (name "/PE2") (class "Default")
      (node (ref "SV6") (pin "3") (pinfunction "3_3") (pintype "passive"))
      (node (ref "U1") (pin "37") (pinfunction "PE2_37") (pintype "bidirectional"))
    )
    (net (code "32") (name "/PE3") (class "Default")
      (node (ref "SV7") (pin "3") (pinfunction "3_3") (pintype "passive"))
      (node (ref "U1") (pin "38") (pinfunction "PE3_38") (pintype "bidirectional"))
    )
    (net (code "33") (name "/PE4") (class "Default")
      (node (ref "L4") (pin "A") (pinfunction "A_A") (pintype "passive"))
      (node (ref "U1") (pin "39") (pinfunction "PE4_39") (pintype "bidirectional"))
    )
    (net (code "34") (name "/PE5") (class "Default")
      (node (ref "L3") (pin "A") (pinfunction "A_A") (pintype "passive"))
      (node (ref "U1") (pin "40") (pinfunction "PE5_40") (pintype "bidirectional"))
    )
    (net (code "35") (name "/PF6") (class "Default")
      (node (ref "TESTSW-R2") (pin "2") (pinfunction "2_2") (pintype "passive"))
      (node (ref "U1") (pin "51") (pinfunction "PF6_51") (pintype "bidirectional"))
      (node (ref "XMEGA-TEST2") (pin "3") (pinfunction "3_3") (pintype "passive"))
      (node (ref "XMEGA-TEST2") (pin "4") (pinfunction "4_4") (pintype "passive"))
    )
    (net (code "36") (name "/PF7") (class "Default")
      (node (ref "TESTSW-R1") (pin "2") (pinfunction "2_2") (pintype "passive"))
      (node (ref "U1") (pin "52") (pinfunction "PF7_52") (pintype "bidirectional"))
      (node (ref "XMEGA-TEST1") (pin "3") (pinfunction "3_3") (pintype "passive"))
      (node (ref "XMEGA-TEST1") (pin "4") (pinfunction "4_4") (pintype "passive"))
    )
    (net (code "37") (name "/PH2") (class "Default")
      (node (ref "CHECKLED") (pin "RED") (pinfunction "RED_RED") (pintype "bidirectional"))
      (node (ref "U1") (pin "57") (pinfunction "PH2_57") (pintype "bidirectional"))
    )
    (net (code "38") (name "/PH3") (class "Default")
      (node (ref "CHECKLED") (pin "GREEN") (pinfunction "GREEN_GREEN") (pintype "bidirectional"))
      (node (ref "U1") (pin "58") (pinfunction "PH3_58") (pintype "bidirectional"))
    )
    (net (code "39") (name "/PH4") (class "Default")
      (node (ref "CHECKLED") (pin "BLUE") (pinfunction "BLUE_BLUE") (pintype "bidirectional"))
      (node (ref "U1") (pin "59") (pinfunction "PH4_59") (pintype "bidirectional"))
    )
    (net (code "40") (name "/PH6") (class "Default")
      (node (ref "U1") (pin "61") (pinfunction "PH6_61") (pintype "bidirectional"))
    )
    (net (code "41") (name "/PH7") (class "Default")
      (node (ref "U1") (pin "62") (pinfunction "PH7_62") (pintype "bidirectional"))
    )
    (net (code "42") (name "/PJ0") (class "Default")
      (node (ref "TOUCH1") (pin "P$1") (pinfunction "1_P$1") (pintype "bidirectional"))
    )
    (net (code "43") (name "/PJ4") (class "Default")
      (node (ref "I2CLCD") (pin "4") (pinfunction "4_4") (pintype "passive"))
      (node (ref "U1") (pin "69") (pinfunction "PJ4_69") (pintype "bidirectional"))
    )
    (net (code "44") (name "/PJ5") (class "Default")
      (node (ref "TOUCH2") (pin "P$1") (pinfunction "1_P$1") (pintype "bidirectional"))
      (node (ref "U1") (pin "70") (pinfunction "PJ5_70") (pintype "bidirectional"))
    )
    (net (code "45") (name "/PK5") (class "Default")
      (node (ref "SV4") (pin "3") (pinfunction "3_3") (pintype "passive"))
      (node (ref "U1") (pin "80") (pinfunction "PK5_80") (pintype "bidirectional"))
    )
    (net (code "46") (name "/RANGE") (class "Default")
      (node (ref "CN2") (pin "P$6") (pinfunction "6_P$6") (pintype "bidirectional"))
      (node (ref "U1") (pin "65") (pinfunction "PJ0_65") (pintype "bidirectional"))
    )
    (net (code "47") (name "/RESET-M1") (class "Default")
      (node (ref "M1-R1") (pin "1") (pinfunction "1_1") (pintype "passive"))
      (node (ref "MEGA2") (pin "29") (pinfunction "PC6(/RESET)_29") (pintype "bidirectional"))
      (node (ref "RESET-MEGA1") (pin "1") (pinfunction "1_1") (pintype "passive"))
      (node (ref "RESET-MEGA1") (pin "2") (pinfunction "2_2") (pintype "passive"))
      (node (ref "S1") (pin "1") (pinfunction "1_1") (pintype "passive"))
    )
    (net (code "48") (name "/RESET-M2") (class "Default")
      (node (ref "M2-R1") (pin "1") (pinfunction "1_1") (pintype "passive"))
      (node (ref "MEGA1") (pin "29") (pinfunction "PC6(/RESET)_29") (pintype "bidirectional"))
      (node (ref "RESET-MEGA2") (pin "1") (pinfunction "1_1") (pintype "passive"))
      (node (ref "RESET-MEGA2") (pin "2") (pinfunction "2_2") (pintype "passive"))
      (node (ref "S1") (pin "2") (pinfunction "1_2") (pintype "passive"))
    )
    (net (code "49") (name "/RXDM1") (class "Default")
      (node (ref "MEGA2") (pin "30") (pinfunction "PD0(RXD)_30") (pintype "bidirectional"))
      (node (ref "S1") (pin "6") (pinfunction "1_6") (pintype "passive"))
    )
    (net (code "50") (name "/RXDM2") (class "Default")
      (node (ref "MEGA1") (pin "30") (pinfunction "PD0(RXD)_30") (pintype "bidirectional"))
      (node (ref "S1") (pin "8") (pinfunction "1_8") (pintype "passive"))
    )
    (net (code "51") (name "/RXDX1") (class "Default")
      (node (ref "S1") (pin "4") (pinfunction "1_4") (pintype "passive"))
      (node (ref "U1") (pin "17") (pinfunction "PC2_17") (pintype "bidirectional"))
    )
    (net (code "52") (name "/RXDX2") (class "Default")
      (node (ref "FT234X") (pin "P$2") (pinfunction "2_P$2") (pintype "bidirectional"))
      (node (ref "TXD-LED1") (pin "A") (pinfunction "A_A") (pintype "passive"))
      (node (ref "U1") (pin "47") (pinfunction "PF2_47") (pintype "bidirectional"))
    )
    (net (code "53") (name "/SCK") (class "Default")
      (node (ref "MEGA1") (pin "17") (pinfunction "PB5(SCK)_17") (pintype "bidirectional"))
      (node (ref "MEGA2") (pin "17") (pinfunction "PB5(SCK)_17") (pintype "bidirectional"))
      (node (ref "SPI-SW") (pin "5") (pinfunction "5_5") (pintype "passive"))
      (node (ref "U1") (pin "22") (pinfunction "PC7_22") (pintype "bidirectional"))
    )
    (net (code "54") (name "/SCL_C") (class "Default")
      (node (ref "SERMO1") (pin "P$3") (pinfunction "3_P$3") (pintype "bidirectional"))
      (node (ref "U1") (pin "16") (pinfunction "PC1_16") (pintype "bidirectional"))
    )
    (net (code "55") (name "/SCL_D") (class "Default")
      (node (ref "SERMO2") (pin "P$3") (pinfunction "3_P$3") (pintype "bidirectional"))
      (node (ref "U1") (pin "26") (pinfunction "PD1_26") (pintype "bidirectional"))
    )
    (net (code "56") (name "/SCL_F") (class "Default")
      (node (ref "I2CLCD") (pin "7") (pinfunction "7_7") (pintype "passive"))
      (node (ref "LCD-I2C") (pin "3") (pinfunction "3_3") (pintype "passive"))
      (node (ref "SW-R3") (pin "1") (pinfunction "1_1") (pintype "passive"))
      (node (ref "U1") (pin "46") (pinfunction "PF1_46") (pintype "bidirectional"))
    )
    (net (code "57") (name "/SDA_C") (class "Default")
      (node (ref "SERMO1") (pin "P$4") (pinfunction "4_P$4") (pintype "bidirectional"))
      (node (ref "U1") (pin "15") (pinfunction "PC0_15") (pintype "bidirectional"))
    )
    (net (code "58") (name "/SDA_D") (class "Default")
      (node (ref "SERMO2") (pin "P$4") (pinfunction "4_P$4") (pintype "bidirectional"))
      (node (ref "U1") (pin "25") (pinfunction "PD0_25") (pintype "bidirectional"))
    )
    (net (code "59") (name "/SDA_F") (class "Default")
      (node (ref "I2CLCD") (pin "8") (pinfunction "8_8") (pintype "passive"))
      (node (ref "I2CLCD") (pin "9") (pinfunction "9_9") (pintype "passive"))
      (node (ref "LCD-I2C") (pin "4") (pinfunction "4_4") (pintype "passive"))
      (node (ref "SW-R4") (pin "1") (pinfunction "1_1") (pintype "passive"))
      (node (ref "U1") (pin "45") (pinfunction "PF0_45") (pintype "bidirectional"))
    )
    (net (code "60") (name "/SERVO") (class "Default")
      (node (ref "SV8") (pin "3") (pinfunction "3_3") (pintype "passive"))
      (node (ref "U1") (pin "100") (pinfunction "PA5_100") (pintype "bidirectional"))
    )
    (net (code "61") (name "/SS1") (class "Default")
      (node (ref "MEGA1") (pin "14") (pinfunction "PB2(SS/OC1B)_14") (pintype "bidirectional"))
      (node (ref "U1") (pin "11") (pinfunction "PB6_11") (pintype "bidirectional"))
    )
    (net (code "62") (name "/SS2") (class "Default")
      (node (ref "MEGA2") (pin "14") (pinfunction "PB2(SS/OC1B)_14") (pintype "bidirectional"))
      (node (ref "U1") (pin "12") (pinfunction "PB7_12") (pintype "bidirectional"))
    )
    (net (code "63") (name "/TXDM1") (class "Default")
      (node (ref "MEGA2") (pin "31") (pinfunction "PD1(TXD)_31") (pintype "bidirectional"))
      (node (ref "S1") (pin "5") (pinfunction "1_5") (pintype "passive"))
    )
    (net (code "64") (name "/TXDM2") (class "Default")
      (node (ref "MEGA1") (pin "31") (pinfunction "PD1(TXD)_31") (pintype "bidirectional"))
      (node (ref "S1") (pin "7") (pinfunction "1_7") (pintype "passive"))
    )
    (net (code "65") (name "/TXDX1") (class "Default")
      (node (ref "S1") (pin "3") (pinfunction "1_3") (pintype "passive"))
      (node (ref "U1") (pin "18") (pinfunction "PC3_18") (pintype "bidirectional"))
    )
    (net (code "66") (name "/TXDX2") (class "Default")
      (node (ref "FT234X") (pin "P$1") (pinfunction "1_P$1") (pintype "bidirectional"))
      (node (ref "RXD-LED1") (pin "A") (pinfunction "A_A") (pintype "passive"))
      (node (ref "U1") (pin "48") (pinfunction "PF3_48") (pintype "bidirectional"))
    )
    (net (code "67") (name "GND") (class "Default")
      (node (ref "3.3C1") (pin "-") (pinfunction "-_-") (pintype "passive"))
      (node (ref "3.3C2") (pin "2") (pinfunction "2_2") (pintype "passive"))
      (node (ref "3.3C3") (pin "2") (pinfunction "2_2") (pintype "passive"))
      (node (ref "3.3C4") (pin "2") (pinfunction "2_2") (pintype "passive"))
      (node (ref "3.3C5") (pin "2") (pinfunction "2_2") (pintype "passive"))
      (node (ref "3.3C6") (pin "-") (pinfunction "-_-") (pintype "passive"))
      (node (ref "3.3V-REGU") (pin "GND") (pinfunction "GND_GND") (pintype "input"))
      (node (ref "5C11") (pin "-") (pinfunction "-_-") (pintype "passive"))
      (node (ref "5C12") (pin "2") (pinfunction "2_2") (pintype "passive"))
      (node (ref "5C13") (pin "2") (pinfunction "2_2") (pintype "passive"))
      (node (ref "5C14") (pin "2") (pinfunction "2_2") (pintype "passive"))
      (node (ref "5C15") (pin "2") (pinfunction "2_2") (pintype "passive"))
      (node (ref "5C16") (pin "-") (pinfunction "-_-") (pintype "passive"))
      (node (ref "5V-REGU") (pin "GND") (pinfunction "GND_GND") (pintype "input"))
      (node (ref "CN2") (pin "P$2") (pinfunction "2_P$2") (pintype "bidirectional"))
      (node (ref "DEVEL-R1") (pin "1") (pinfunction "1_1") (pintype "passive"))
      (node (ref "DEVEL-R2") (pin "1") (pinfunction "1_1") (pintype "passive"))
      (node (ref "ERROR1-R") (pin "1") (pinfunction "1_1") (pintype "passive"))
      (node (ref "ERROR2-R") (pin "1") (pinfunction "1_1") (pintype "passive"))
      (node (ref "FAN-GND") (pin "1") (pinfunction "P_1") (pintype "passive"))
      (node (ref "FT232-R2") (pin "1") (pinfunction "1_1") (pintype "passive"))
      (node (ref "FT232-R3") (pin "1") (pinfunction "1_1") (pintype "passive"))
      (node (ref "FT232-R4") (pin "1") (pinfunction "1_1") (pintype "passive"))
      (node (ref "FT232-R5") (pin "1") (pinfunction "1_1") (pintype "passive"))
      (node (ref "FT232USBCON") (pin "5") (pinfunction "5_5") (pintype "passive"))
      (node (ref "FT232USBCON") (pin "M1") (pinfunction "S1_M1") (pintype "passive"))
      (node (ref "FT234-R1") (pin "1") (pinfunction "1_1") (pintype "passive"))
      (node (ref "FT234-R2") (pin "1") (pinfunction "1_1") (pintype "passive"))
      (node (ref "FT234X") (pin "P$3") (pinfunction "3_P$3") (pintype "bidirectional"))
      (node (ref "GND-CHK") (pin "1") (pinfunction "P_1") (pintype "passive"))
      (node (ref "GND-CHK1") (pin "1") (pinfunction "P_1") (pintype "passive"))
      (node (ref "I2CLCD") (pin "1") (pinfunction "1_1") (pintype "passive"))
      (node (ref "IC5") (pin "18") (pinfunction "GND_18") (pintype "power_in"))
      (node (ref "IC5") (pin "21") (pinfunction "GND_21") (pintype "power_in"))
      (node (ref "IC5") (pin "25") (pinfunction "GND_25") (pintype "power_in"))
      (node (ref "IC5") (pin "26") (pinfunction "TEST_26") (pintype "input"))
      (node (ref "IC5") (pin "7") (pinfunction "GND_7") (pintype "power_in"))
      (node (ref "LCD-I2C") (pin "5") (pinfunction "5_5") (pintype "passive"))
      (node (ref "MAIN-LED") (pin "P$2") (pinfunction "2_P$2") (pintype "bidirectional"))
      (node (ref "MAIN-LED1") (pin "P$2") (pinfunction "2_P$2") (pintype "bidirectional"))
      (node (ref "MEGA1") (pin "21") (pinfunction "GND_21") (pintype "power_in"))
      (node (ref "MEGA1") (pin "3") (pinfunction "GND_3") (pintype "power_in"))
      (node (ref "MEGA1") (pin "5") (pinfunction "GND_5") (pintype "power_in"))
      (node (ref "MEGA1-C1") (pin "1") (pinfunction "1_1") (pintype "passive"))
      (node (ref "MEGA2") (pin "21") (pinfunction "GND_21") (pintype "power_in"))
      (node (ref "MEGA2") (pin "3") (pinfunction "GND_3") (pintype "power_in"))
      (node (ref "MEGA2") (pin "5") (pinfunction "GND_5") (pintype "power_in"))
      (node (ref "MEGA2-C1") (pin "2") (pinfunction "2_2") (pintype "passive"))
      (node (ref "MOTOR-SUPPLY") (pin "2") (pinfunction "KL_2") (pintype "passive"))
      (node (ref "MOTORDRIVER") (pin "13") (pinfunction "13_13") (pintype "passive"))
      (node (ref "PAD2") (pin "1") (pinfunction "P_1") (pintype "passive"))
      (node (ref "POWER-LED") (pin "C") (pinfunction "C_C") (pintype "passive"))
      (node (ref "Q1") (pin "2") (pinfunction "VSS_2") (pintype "power_in"))
      (node (ref "Q2") (pin "2") (pinfunction "VSS_2") (pintype "power_in"))
      (node (ref "RESET-MEGA1") (pin "3") (pinfunction "3_3") (pintype "passive"))
      (node (ref "RESET-MEGA1") (pin "4") (pinfunction "4_4") (pintype "passive"))
      (node (ref "RESET-MEGA2") (pin "3") (pinfunction "3_3") (pintype "passive"))
      (node (ref "RESET-MEGA2") (pin "4") (pinfunction "4_4") (pintype "passive"))
      (node (ref "RESET-XMEGA") (pin "3") (pinfunction "3_3") (pintype "passive"))
      (node (ref "RESET-XMEGA") (pin "4") (pinfunction "4_4") (pintype "passive"))
      (node (ref "RO1") (pin "P$1") (pinfunction "1_P$1") (pintype "bidirectional"))
      (node (ref "RO2") (pin "P$1") (pinfunction "1_P$1") (pintype "bidirectional"))
      (node (ref "SERMO") (pin "1") (pinfunction "1_1") (pintype "passive"))
      (node (ref "SERMO1") (pin "P$1") (pinfunction "1_P$1") (pintype "bidirectional"))
      (node (ref "SERMO2") (pin "P$1") (pinfunction "1_P$1") (pintype "bidirectional"))
      (node (ref "SUOPPLY-SW1") (pin "P$2") (pinfunction "2_P$2") (pintype "bidirectional"))
      (node (ref "SUPPLY") (pin "2") (pinfunction "KL_2") (pintype "passive"))
      (node (ref "SV1") (pin "1") (pinfunction "1_1") (pintype "passive"))
      (node (ref "SV2") (pin "1") (pinfunction "1_1") (pintype "passive"))
      (node (ref "SV3") (pin "6") (pinfunction "6_6") (pintype "passive"))
      (node (ref "SV4") (pin "1") (pinfunction "1_1") (pintype "passive"))
      (node (ref "SV5") (pin "1") (pinfunction "1_1") (pintype "passive"))
      (node (ref "SV6") (pin "1") (pinfunction "1_1") (pintype "passive"))
      (node (ref "SV7") (pin "1") (pinfunction "1_1") (pintype "passive"))
      (node (ref "SV8") (pin "1") (pinfunction "1_1") (pintype "passive"))
      (node (ref "SW-LED") (pin "P$1") (pinfunction "1_P$1") (pintype "bidirectional"))
      (node (ref "SW-LED") (pin "P$3") (pinfunction "3_P$3") (pintype "bidirectional"))
      (node (ref "SW-RED") (pin "P$3") (pinfunction "3_P$3") (pintype "bidirectional"))
      (node (ref "TESTSW-R1") (pin "1") (pinfunction "1_1") (pintype "passive"))
      (node (ref "TESTSW-R2") (pin "1") (pinfunction "1_1") (pintype "passive"))
      (node (ref "TOUCH1") (pin "P$3") (pinfunction "3_P$3") (pintype "bidirectional"))
      (node (ref "TOUCH2") (pin "P$3") (pinfunction "3_P$3") (pintype "bidirectional"))
      (node (ref "U1") (pin "13") (pinfunction "GND_13") (pintype "power_in"))
      (node (ref "U1") (pin "23") (pinfunction "GND_23") (pintype "power_in"))
      (node (ref "U1") (pin "3") (pinfunction "GND_3") (pintype "power_in"))
      (node (ref "U1") (pin "33") (pinfunction "GND_33") (pintype "power_in"))
      (node (ref "U1") (pin "43") (pinfunction "GND_43") (pintype "power_in"))
      (node (ref "U1") (pin "53") (pinfunction "GND_53") (pintype "power_in"))
      (node (ref "U1") (pin "63") (pinfunction "GND_63") (pintype "power_in"))
      (node (ref "U1") (pin "73") (pinfunction "GND_73") (pintype "power_in"))
      (node (ref "U1") (pin "84") (pinfunction "GND_84") (pintype "power_in"))
      (node (ref "U1") (pin "93") (pinfunction "GND_93") (pintype "power_in"))
      (node (ref "VOLTAGE-METER") (pin "P$2") (pinfunction "2_P$2") (pintype "bidirectional"))
      (node (ref "X1") (pin "2") (pinfunction "2_2") (pintype "passive"))
      (node (ref "XMEGA-C1") (pin "2") (pinfunction "2_2") (pintype "passive"))
    )
    (net (code "68") (name "Net-(CHECKLED-PadANODE)") (class "Default")
      (node (ref "CHECKLED") (pin "ANODE") (pinfunction "ANODE_ANODE") (pintype "bidirectional"))
      (node (ref "R150") (pin "1") (pinfunction "1_1") (pintype "passive"))
    )
    (net (code "69") (name "Net-(FT-POWERLED-PadC)") (class "Default")
      (node (ref "FT-POWERLED") (pin "C") (pinfunction "C_C") (pintype "passive"))
      (node (ref "FT232-R3") (pin "2") (pinfunction "2_2") (pintype "passive"))
    )
    (net (code "70") (name "Net-(FT232-R4-Pad2)") (class "Default")
      (node (ref "FT232-R4") (pin "2") (pinfunction "2_2") (pintype "passive"))
      (node (ref "L1") (pin "C") (pinfunction "C_C") (pintype "passive"))
    )
    (net (code "71") (name "Net-(FT232-R5-Pad2)") (class "Default")
      (node (ref "FT232-R5") (pin "2") (pinfunction "2_2") (pintype "passive"))
      (node (ref "L2") (pin "C") (pinfunction "C_C") (pintype "passive"))
    )
    (net (code "72") (name "Net-(FT232-R6-Pad2)") (class "Default")
      (node (ref "FT232-R6") (pin "2") (pinfunction "2_2") (pintype "passive"))
      (node (ref "FT232USBCON") (pin "3") (pinfunction "3_3") (pintype "passive"))
    )
    (net (code "73") (name "Net-(FT232-R7-Pad2)") (class "Default")
      (node (ref "FT232-R7") (pin "2") (pinfunction "2_2") (pintype "passive"))
      (node (ref "FT232USBCON") (pin "2") (pinfunction "2_2") (pintype "passive"))
    )
    (net (code "74") (name "Net-(FT234-R1-Pad2)") (class "Default")
      (node (ref "FT234-R1") (pin "2") (pinfunction "2_2") (pintype "passive"))
      (node (ref "TXD-LED1") (pin "C") (pinfunction "C_C") (pintype "passive"))
    )
    (net (code "75") (name "Net-(FT234-R2-Pad2)") (class "Default")
      (node (ref "FT234-R2") (pin "2") (pinfunction "2_2") (pintype "passive"))
      (node (ref "RXD-LED1") (pin "C") (pinfunction "C_C") (pintype "passive"))
    )
    (net (code "76") (name "Net-(IC5-3V3OUT)") (class "Default")
      (node (ref "IC5") (pin "17") (pinfunction "3V3OUT_17") (pintype "output"))
      (node (ref "IC5") (pin "4") (pinfunction "VCCIO_4") (pintype "power_in"))
    )
    (net (code "77") (name "Net-(IC5-USBDM)") (class "Default")
      (node (ref "FT232-R7") (pin "1") (pinfunction "1_1") (pintype "passive"))
      (node (ref "IC5") (pin "16") (pinfunction "USBDM_16") (pintype "bidirectional"))
    )
    (net (code "78") (name "Net-(IC5-USBDP)") (class "Default")
      (node (ref "FT232-R6") (pin "1") (pinfunction "1_1") (pintype "passive"))
      (node (ref "IC5") (pin "15") (pinfunction "USBDP_15") (pintype "bidirectional"))
    )
    (net (code "79") (name "Net-(IC5-VCC)") (class "Default")
      (node (ref "FT-POWERLED") (pin "A") (pinfunction "A_A") (pintype "passive"))
      (node (ref "FT232-R1") (pin "2") (pinfunction "2_2") (pintype "passive"))
      (node (ref "FT232USBCON") (pin "1") (pinfunction "1_1") (pintype "passive"))
      (node (ref "IC5") (pin "20") (pinfunction "VCC_20") (pintype "power_in"))
    )
    (net (code "80") (name "Net-(IC5-~{CTS})") (class "Default")
      (node (ref "IC5") (pin "11") (pinfunction "~{CTS}_11") (pintype "input"))
      (node (ref "SPI-SW") (pin "1") (pinfunction "1_1") (pintype "passive"))
    )
    (net (code "81") (name "Net-(IC5-~{DCD})") (class "Default")
      (node (ref "IC5") (pin "10") (pinfunction "~{DCD}_10") (pintype "input"))
      (node (ref "SPI-SW") (pin "3") (pinfunction "3_3") (pintype "passive"))
    )
    (net (code "82") (name "Net-(IC5-~{DSR})") (class "Default")
      (node (ref "IC5") (pin "9") (pinfunction "~{DSR}_9") (pintype "input"))
      (node (ref "SPI-SW") (pin "2") (pinfunction "2_2") (pintype "passive"))
    )
    (net (code "83") (name "Net-(IC5-~{RESET})") (class "Default")
      (node (ref "FT232-R1") (pin "1") (pinfunction "1_1") (pintype "passive"))
      (node (ref "FT232-R2") (pin "2") (pinfunction "2_2") (pintype "passive"))
      (node (ref "IC5") (pin "19") (pinfunction "~{RESET}_19") (pintype "input"))
    )
    (net (code "84") (name "Net-(L3-C)") (class "Default")
      (node (ref "ERROR1-R") (pin "2") (pinfunction "2_2") (pintype "passive"))
      (node (ref "L3") (pin "K") (pinfunction "C_K") (pintype "passive"))
    )
    (net (code "85") (name "Net-(L4-C)") (class "Default")
      (node (ref "ERROR2-R") (pin "2") (pinfunction "2_2") (pintype "passive"))
      (node (ref "L4") (pin "K") (pinfunction "C_K") (pintype "passive"))
    )
    (net (code "86") (name "Net-(MAIN-LED1-1)") (class "Default")
      (node (ref "LED-R1") (pin "1") (pinfunction "1_1") (pintype "passive"))
      (node (ref "MAIN-LED1") (pin "P$1") (pinfunction "1_P$1") (pintype "bidirectional"))
    )
    (net (code "87") (name "Net-(MEGA1-PB6(XTAL1{slash}TOSC1))") (class "Default")
      (node (ref "MEGA1") (pin "7") (pinfunction "PB6(XTAL1/TOSC1)_7") (pintype "bidirectional"))
      (node (ref "Q1") (pin "1") (pinfunction "1_1") (pintype "output"))
    )
    (net (code "88") (name "Net-(MEGA1-PB7(XTAL2{slash}TOSC2))") (class "Default")
      (node (ref "MEGA1") (pin "8") (pinfunction "PB7(XTAL2/TOSC2)_8") (pintype "bidirectional"))
      (node (ref "Q1") (pin "3") (pinfunction "3_3") (pintype "input"))
    )
    (net (code "89") (name "Net-(MEGA1-PD2(INT0))") (class "Default")
      (node (ref "MEGA1") (pin "32") (pinfunction "PD2(INT0)_32") (pintype "bidirectional"))
      (node (ref "RO2") (pin "P$3") (pinfunction "3_P$3") (pintype "bidirectional"))
    )
    (net (code "90") (name "Net-(MEGA2-PB6(XTAL1{slash}TOSC1))") (class "Default")
      (node (ref "MEGA2") (pin "7") (pinfunction "PB6(XTAL1/TOSC1)_7") (pintype "bidirectional"))
      (node (ref "Q2") (pin "1") (pinfunction "1_1") (pintype "output"))
    )
    (net (code "91") (name "Net-(MEGA2-PB7(XTAL2{slash}TOSC2))") (class "Default")
      (node (ref "MEGA2") (pin "8") (pinfunction "PB7(XTAL2/TOSC2)_8") (pintype "bidirectional"))
      (node (ref "Q2") (pin "3") (pinfunction "3_3") (pintype "input"))
    )
    (net (code "92") (name "Net-(MEGA2-PD2(INT0))") (class "Default")
      (node (ref "MEGA2") (pin "32") (pinfunction "PD2(INT0)_32") (pintype "bidirectional"))
      (node (ref "RO1") (pin "P$3") (pinfunction "3_P$3") (pintype "bidirectional"))
    )
    (net (code "93") (name "Net-(MOTOR-SUPPLYA-KL)") (class "Default")
      (node (ref "MOTOR-SUPPLY") (pin "1") (pinfunction "KL_1") (pintype "passive"))
      (node (ref "MOTOR-SW") (pin "3") (pinfunction "S_3") (pintype "passive"))
    )
    (net (code "94") (name "Net-(POWER-LED-PadA)") (class "Default")
      (node (ref "POWER-LED") (pin "A") (pinfunction "A_A") (pintype "passive"))
      (node (ref "POWER-LEDR") (pin "1") (pinfunction "1_1") (pintype "passive"))
    )
    (net (code "95") (name "Net-(SUOPPLY-SW1-1)") (class "Default")
      (node (ref "M2-R2") (pin "1") (pinfunction "1_1") (pintype "passive"))
      (node (ref "Q3") (pin "G") (pinfunction "G_G") (pintype "passive"))
      (node (ref "SUOPPLY-SW1") (pin "P$1") (pinfunction "1_P$1") (pintype "bidirectional"))
    )
    (net (code "96") (name "Net-(SUPPLYA-KL)") (class "Default")
      (node (ref "M2-R2") (pin "2") (pinfunction "2_2") (pintype "passive"))
      (node (ref "Q3") (pin "S") (pinfunction "S_S") (pintype "passive"))
      (node (ref "SUPPLY") (pin "1") (pinfunction "KL_1") (pintype "passive"))
      (node (ref "X1") (pin "1") (pinfunction "1_1") (pintype "passive"))
    )
    (net (code "97") (name "Net-(SW-LED-2)") (class "Default")
      (node (ref "SW-LED") (pin "P$2") (pinfunction "2_P$2") (pintype "bidirectional"))
      (node (ref "SW-R1") (pin "1") (pinfunction "1_1") (pintype "passive"))
    )
    (net (code "98") (name "Net-(U1-PDI)") (class "Default")
      (node (ref "SV3") (pin "1") (pinfunction "1_1") (pintype "passive"))
      (node (ref "U1") (pin "89") (pinfunction "PDI_89") (pintype "bidirectional"))
    )
    (net (code "99") (name "Net-(U1-PH5)") (class "Default")
      (node (ref "SV1") (pin "3") (pinfunction "3_3") (pintype "passive"))
      (node (ref "U1") (pin "60") (pinfunction "PH5_60") (pintype "bidirectional"))
    )
    (net (code "100") (name "Net-(U1-PK1)") (class "Default")
      (node (ref "SV2") (pin "3") (pinfunction "3_3") (pintype "passive"))
      (node (ref "U1") (pin "76") (pinfunction "PK1_76") (pintype "bidirectional"))
    )
    (net (code "101") (name "unconnected-(CN2-8-PadP$8)") (class "Default")
      (node (ref "CN2") (pin "P$8") (pinfunction "8_P$8") (pintype "bidirectional"))
    )
    (net (code "102") (name "unconnected-(FT232USBCON-Pad4)") (class "Default")
      (node (ref "FT232USBCON") (pin "4") (pinfunction "4_4") (pintype "passive"))
    )
    (net (code "103") (name "unconnected-(FT232USBCONB-S2-PadM2)") (class "Default")
      (node (ref "FT232USBCON") (pin "M2") (pinfunction "S2_M2") (pintype "passive"))
    )
    (net (code "104") (name "unconnected-(FT232USBCONB-S3-PadM3)") (class "Default")
      (node (ref "FT232USBCON") (pin "M3") (pinfunction "S3_M3") (pintype "passive"))
    )
    (net (code "105") (name "unconnected-(FT232USBCONB-S4-PadM4)") (class "Default")
      (node (ref "FT232USBCON") (pin "M4") (pinfunction "S4_M4") (pintype "passive"))
    )
    (net (code "106") (name "unconnected-(FT234X-4-PadP$4)") (class "Default")
      (node (ref "FT234X") (pin "P$4") (pinfunction "4_P$4") (pintype "bidirectional"))
    )
    (net (code "107") (name "unconnected-(I2CLCD-Pad3)") (class "Default")
      (node (ref "I2CLCD") (pin "3") (pinfunction "3_3") (pintype "passive"))
    )
    (net (code "108") (name "unconnected-(I2CLCD-Pad5)") (class "Default")
      (node (ref "I2CLCD") (pin "5") (pinfunction "5_5") (pintype "passive"))
    )
    (net (code "109") (name "unconnected-(I2CLCD-Pad6)") (class "Default")
      (node (ref "I2CLCD") (pin "6") (pinfunction "6_6") (pintype "passive"))
    )
    (net (code "110") (name "unconnected-(I2CLCD-Pad10)") (class "Default")
      (node (ref "I2CLCD") (pin "10") (pinfunction "10_10") (pintype "passive"))
    )
    (net (code "111") (name "unconnected-(I2CLCD-Pad11)") (class "Default")
      (node (ref "I2CLCD") (pin "11") (pinfunction "11_11") (pintype "passive"))
    )
    (net (code "112") (name "unconnected-(I2CLCD-Pad12)") (class "Default")
      (node (ref "I2CLCD") (pin "12") (pinfunction "12_12") (pintype "passive"))
    )
    (net (code "113") (name "unconnected-(I2CLCD-Pad13)") (class "Default")
      (node (ref "I2CLCD") (pin "13") (pinfunction "13_13") (pintype "passive"))
    )
    (net (code "114") (name "unconnected-(I2CLCD-Pad14)") (class "Default")
      (node (ref "I2CLCD") (pin "14") (pinfunction "14_14") (pintype "passive"))
    )
    (net (code "115") (name "unconnected-(IC5-CBUS0-Pad23)") (class "Default")
      (node (ref "IC5") (pin "23") (pinfunction "CBUS0_23") (pintype "bidirectional"))
    )
    (net (code "116") (name "unconnected-(IC5-CBUS1-Pad22)") (class "Default")
      (node (ref "IC5") (pin "22") (pinfunction "CBUS1_22") (pintype "bidirectional"))
    )
    (net (code "117") (name "unconnected-(IC5-CBUS2-Pad13)") (class "Default")
      (node (ref "IC5") (pin "13") (pinfunction "CBUS2_13") (pintype "bidirectional"))
    )
    (net (code "118") (name "unconnected-(IC5-CBUS3-Pad14)") (class "Default")
      (node (ref "IC5") (pin "14") (pinfunction "CBUS3_14") (pintype "bidirectional"))
    )
    (net (code "119") (name "unconnected-(IC5-CBUS4-Pad12)") (class "Default")
      (node (ref "IC5") (pin "12") (pinfunction "CBUS4_12") (pintype "bidirectional"))
    )
    (net (code "120") (name "unconnected-(IC5-OSCI-Pad27)") (class "Default")
      (node (ref "IC5") (pin "27") (pinfunction "OSCI_27") (pintype "input"))
    )
    (net (code "121") (name "unconnected-(IC5-OSCO-Pad28)") (class "Default")
      (node (ref "IC5") (pin "28") (pinfunction "OSCO_28") (pintype "output"))
    )
    (net (code "122") (name "unconnected-(IC5-~{DTR}-Pad2)") (class "Default")
      (node (ref "IC5") (pin "2") (pinfunction "~{DTR}_2") (pintype "output"))
    )
    (net (code "123") (name "unconnected-(IC5-~{RTS}-Pad3)") (class "Default")
      (node (ref "IC5") (pin "3") (pinfunction "~{RTS}_3") (pintype "output"))
    )
    (net (code "124") (name "unconnected-(MEGA1-ADC6-Pad19)") (class "Default")
      (node (ref "MEGA1") (pin "19") (pinfunction "ADC6_19") (pintype "bidirectional"))
    )
    (net (code "125") (name "unconnected-(MEGA1-ADC7-Pad22)") (class "Default")
      (node (ref "MEGA1") (pin "22") (pinfunction "ADC7_22") (pintype "bidirectional"))
    )
    (net (code "126") (name "unconnected-(MEGA1-AREF-Pad20)") (class "Default")
      (node (ref "MEGA1") (pin "20") (pinfunction "AREF_20") (pintype "passive"))
    )
    (net (code "127") (name "unconnected-(MEGA1-PB0(ICP)-Pad12)") (class "Default")
      (node (ref "MEGA1") (pin "12") (pinfunction "PB0(ICP)_12") (pintype "bidirectional"))
    )
    (net (code "128") (name "unconnected-(MEGA1-PB1(OC1A)-Pad13)") (class "Default")
      (node (ref "MEGA1") (pin "13") (pinfunction "PB1(OC1A)_13") (pintype "bidirectional"))
    )
    (net (code "129") (name "unconnected-(MEGA1-PC0(ADC0)-Pad23)") (class "Default")
      (node (ref "MEGA1") (pin "23") (pinfunction "PC0(ADC0)_23") (pintype "bidirectional"))
    )
    (net (code "130") (name "unconnected-(MEGA1-PC1(ADC1)-Pad24)") (class "Default")
      (node (ref "MEGA1") (pin "24") (pinfunction "PC1(ADC1)_24") (pintype "bidirectional"))
    )
    (net (code "131") (name "unconnected-(MEGA1-PD3(INT1)-Pad1)") (class "Default")
      (node (ref "MEGA1") (pin "1") (pinfunction "PD3(INT1)_1") (pintype "bidirectional"))
    )
    (net (code "132") (name "unconnected-(MEGA1-PD4(XCK{slash}T0)-Pad2)") (class "Default")
      (node (ref "MEGA1") (pin "2") (pinfunction "PD4(XCK/T0)_2") (pintype "bidirectional"))
    )
    (net (code "133") (name "unconnected-(MEGA1-PD5(T1)-Pad9)") (class "Default")
      (node (ref "MEGA1") (pin "9") (pinfunction "PD5(T1)_9") (pintype "bidirectional"))
    )
    (net (code "134") (name "unconnected-(MEGA1-PD7(AIN1)-Pad11)") (class "Default")
      (node (ref "MEGA1") (pin "11") (pinfunction "PD7(AIN1)_11") (pintype "bidirectional"))
    )
    (net (code "135") (name "unconnected-(MEGA2-ADC6-Pad19)") (class "Default")
      (node (ref "MEGA2") (pin "19") (pinfunction "ADC6_19") (pintype "bidirectional"))
    )
    (net (code "136") (name "unconnected-(MEGA2-ADC7-Pad22)") (class "Default")
      (node (ref "MEGA2") (pin "22") (pinfunction "ADC7_22") (pintype "bidirectional"))
    )
    (net (code "137") (name "unconnected-(MEGA2-AREF-Pad20)") (class "Default")
      (node (ref "MEGA2") (pin "20") (pinfunction "AREF_20") (pintype "passive"))
    )
    (net (code "138") (name "unconnected-(MEGA2-PB0(ICP)-Pad12)") (class "Default")
      (node (ref "MEGA2") (pin "12") (pinfunction "PB0(ICP)_12") (pintype "bidirectional"))
    )
    (net (code "139") (name "unconnected-(MEGA2-PB1(OC1A)-Pad13)") (class "Default")
      (node (ref "MEGA2") (pin "13") (pinfunction "PB1(OC1A)_13") (pintype "bidirectional"))
    )
    (net (code "140") (name "unconnected-(MEGA2-PC0(ADC0)-Pad23)") (class "Default")
      (node (ref "MEGA2") (pin "23") (pinfunction "PC0(ADC0)_23") (pintype "bidirectional"))
    )
    (net (code "141") (name "unconnected-(MEGA2-PC1(ADC1)-Pad24)") (class "Default")
      (node (ref "MEGA2") (pin "24") (pinfunction "PC1(ADC1)_24") (pintype "bidirectional"))
    )
    (net (code "142") (name "unconnected-(MEGA2-PD3(INT1)-Pad1)") (class "Default")
      (node (ref "MEGA2") (pin "1") (pinfunction "PD3(INT1)_1") (pintype "bidirectional"))
    )
    (net (code "143") (name "unconnected-(MEGA2-PD4(XCK{slash}T0)-Pad2)") (class "Default")
      (node (ref "MEGA2") (pin "2") (pinfunction "PD4(XCK/T0)_2") (pintype "bidirectional"))
    )
    (net (code "144") (name "unconnected-(MEGA2-PD5(T1)-Pad9)") (class "Default")
      (node (ref "MEGA2") (pin "9") (pinfunction "PD5(T1)_9") (pintype "bidirectional"))
    )
    (net (code "145") (name "unconnected-(MEGA2-PD7(AIN1)-Pad11)") (class "Default")
      (node (ref "MEGA2") (pin "11") (pinfunction "PD7(AIN1)_11") (pintype "bidirectional"))
    )
    (net (code "146") (name "unconnected-(MOTOR-SW-O-Pad1)") (class "Default")
      (node (ref "MOTOR-SW") (pin "1") (pinfunction "O_1") (pintype "passive"))
    )
    (net (code "147") (name "unconnected-(SUOPPLY-SW1-3-PadP$3)") (class "Default")
      (node (ref "SUOPPLY-SW1") (pin "P$3") (pinfunction "3_P$3") (pintype "bidirectional"))
    )
    (net (code "148") (name "unconnected-(SV3-Pad2)") (class "Default")
      (node (ref "SV3") (pin "2") (pinfunction "2_2") (pintype "passive"))
    )
    (net (code "149") (name "unconnected-(SV3-Pad3)") (class "Default")
      (node (ref "SV3") (pin "3") (pinfunction "3_3") (pintype "passive"))
    )
    (net (code "150") (name "unconnected-(SV3-Pad4)") (class "Default")
      (node (ref "SV3") (pin "4") (pinfunction "4_4") (pintype "passive"))
    )
    (net (code "151") (name "unconnected-(SW-RED-4-PadP$4)") (class "Default")
      (node (ref "SW-RED") (pin "P$4") (pinfunction "4_P$4") (pintype "bidirectional"))
    )
    (net (code "152") (name "unconnected-(U1-PA0-Pad95)") (class "Default")
      (node (ref "U1") (pin "95") (pinfunction "PA0_95") (pintype "bidirectional"))
    )
    (net (code "153") (name "unconnected-(U1-PA1-Pad96)") (class "Default")
      (node (ref "U1") (pin "96") (pinfunction "PA1_96") (pintype "bidirectional"))
    )
    (net (code "154") (name "unconnected-(U1-PA2-Pad97)") (class "Default")
      (node (ref "U1") (pin "97") (pinfunction "PA2_97") (pintype "bidirectional"))
    )
    (net (code "155") (name "unconnected-(U1-PA3-Pad98)") (class "Default")
      (node (ref "U1") (pin "98") (pinfunction "PA3_98") (pintype "bidirectional"))
    )
    (net (code "156") (name "unconnected-(U1-PA4-Pad99)") (class "Default")
      (node (ref "U1") (pin "99") (pinfunction "PA4_99") (pintype "bidirectional"))
    )
    (net (code "157") (name "unconnected-(U1-PB0-Pad5)") (class "Default")
      (node (ref "U1") (pin "5") (pinfunction "PB0_5") (pintype "bidirectional"))
    )
    (net (code "158") (name "unconnected-(U1-PB1-Pad6)") (class "Default")
      (node (ref "U1") (pin "6") (pinfunction "PB1_6") (pintype "bidirectional"))
    )
    (net (code "159") (name "unconnected-(U1-PB2-Pad7)") (class "Default")
      (node (ref "U1") (pin "7") (pinfunction "PB2_7") (pintype "bidirectional"))
    )
    (net (code "160") (name "unconnected-(U1-PB3-Pad8)") (class "Default")
      (node (ref "U1") (pin "8") (pinfunction "PB3_8") (pintype "bidirectional"))
    )
    (net (code "161") (name "unconnected-(U1-PB4-Pad9)") (class "Default")
      (node (ref "U1") (pin "9") (pinfunction "PB4_9") (pintype "bidirectional"))
    )
    (net (code "162") (name "unconnected-(U1-PB5-Pad10)") (class "Default")
      (node (ref "U1") (pin "10") (pinfunction "PB5_10") (pintype "bidirectional"))
    )
    (net (code "163") (name "unconnected-(U1-PC4-Pad19)") (class "Default")
      (node (ref "U1") (pin "19") (pinfunction "PC4_19") (pintype "bidirectional"))
    )
    (net (code "164") (name "unconnected-(U1-PD6-Pad31)") (class "Default")
      (node (ref "U1") (pin "31") (pinfunction "PD6_31") (pintype "bidirectional"))
    )
    (net (code "165") (name "unconnected-(U1-PD7-Pad32)") (class "Default")
      (node (ref "U1") (pin "32") (pinfunction "PD7_32") (pintype "bidirectional"))
    )
    (net (code "166") (name "unconnected-(U1-PE1-Pad36)") (class "Default")
      (node (ref "U1") (pin "36") (pinfunction "PE1_36") (pintype "bidirectional"))
    )
    (net (code "167") (name "unconnected-(U1-PE6-Pad41)") (class "Default")
      (node (ref "U1") (pin "41") (pinfunction "PE6_41") (pintype "bidirectional"))
    )
    (net (code "168") (name "unconnected-(U1-PE7-Pad42)") (class "Default")
      (node (ref "U1") (pin "42") (pinfunction "PE7_42") (pintype "bidirectional"))
    )
    (net (code "169") (name "unconnected-(U1-PF4-Pad49)") (class "Default")
      (node (ref "U1") (pin "49") (pinfunction "PF4_49") (pintype "bidirectional"))
    )
    (net (code "170") (name "unconnected-(U1-PF5-Pad50)") (class "Default")
      (node (ref "U1") (pin "50") (pinfunction "PF5_50") (pintype "bidirectional"))
    )
    (net (code "171") (name "unconnected-(U1-PH0-Pad55)") (class "Default")
      (node (ref "U1") (pin "55") (pinfunction "PH0_55") (pintype "bidirectional"))
    )
    (net (code "172") (name "unconnected-(U1-PH1-Pad56)") (class "Default")
      (node (ref "U1") (pin "56") (pinfunction "PH1_56") (pintype "bidirectional"))
    )
    (net (code "173") (name "unconnected-(U1-PK0-Pad75)") (class "Default")
      (node (ref "U1") (pin "75") (pinfunction "PK0_75") (pintype "bidirectional"))
    )
    (net (code "174") (name "unconnected-(U1-PK2-Pad77)") (class "Default")
      (node (ref "U1") (pin "77") (pinfunction "PK2_77") (pintype "bidirectional"))
    )
    (net (code "175") (name "unconnected-(U1-PK3-Pad78)") (class "Default")
      (node (ref "U1") (pin "78") (pinfunction "PK3_78") (pintype "bidirectional"))
    )
    (net (code "176") (name "unconnected-(U1-PK4-Pad79)") (class "Default")
      (node (ref "U1") (pin "79") (pinfunction "PK4_79") (pintype "bidirectional"))
    )
    (net (code "177") (name "unconnected-(U1-PK6-Pad81)") (class "Default")
      (node (ref "U1") (pin "81") (pinfunction "PK6_81") (pintype "bidirectional"))
    )
    (net (code "178") (name "unconnected-(U1-PK7-Pad82)") (class "Default")
      (node (ref "U1") (pin "82") (pinfunction "PK7_82") (pintype "bidirectional"))
    )
    (net (code "179") (name "unconnected-(U1-PQ0-Pad85)") (class "Default")
      (node (ref "U1") (pin "85") (pinfunction "PQ0_85") (pintype "bidirectional"))
    )
    (net (code "180") (name "unconnected-(U1-PQ1-Pad86)") (class "Default")
      (node (ref "U1") (pin "86") (pinfunction "PQ1_86") (pintype "bidirectional"))
    )
    (net (code "181") (name "unconnected-(U1-PQ2-Pad87)") (class "Default")
      (node (ref "U1") (pin "87") (pinfunction "PQ2_87") (pintype "bidirectional"))
    )
    (net (code "182") (name "unconnected-(U1-PQ3-Pad88)") (class "Default")
      (node (ref "U1") (pin "88") (pinfunction "PQ3_88") (pintype "bidirectional"))
    )
    (net (code "183") (name "unconnected-(U1-PR0-Pad91)") (class "Default")
      (node (ref "U1") (pin "91") (pinfunction "PR0_91") (pintype "bidirectional"))
    )
    (net (code "184") (name "unconnected-(U1-PR1-Pad92)") (class "Default")
      (node (ref "U1") (pin "92") (pinfunction "PR1_92") (pintype "bidirectional"))
    )
    (net (code "185") (name "unconnected-(X1-Pad3)") (class "Default")
      (node (ref "X1") (pin "3") (pinfunction "3_3") (pintype "passive"))
    )
  )
)
